# FlatSat_Final.net
KiCad netlist of a schematic drawn in EAGLE
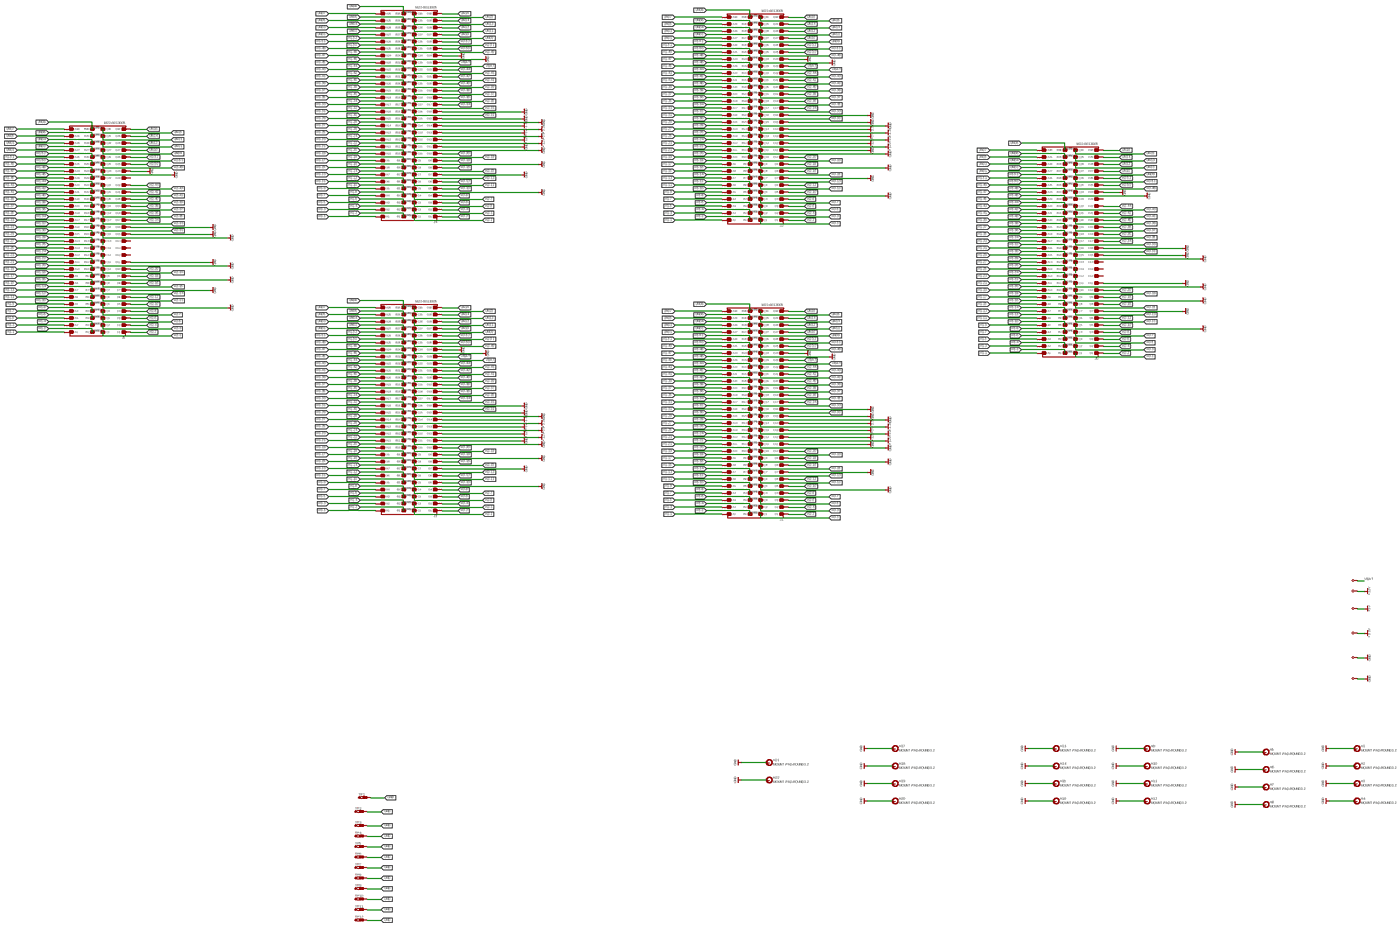
[diagram p0: schematic, sheet 1, overview]
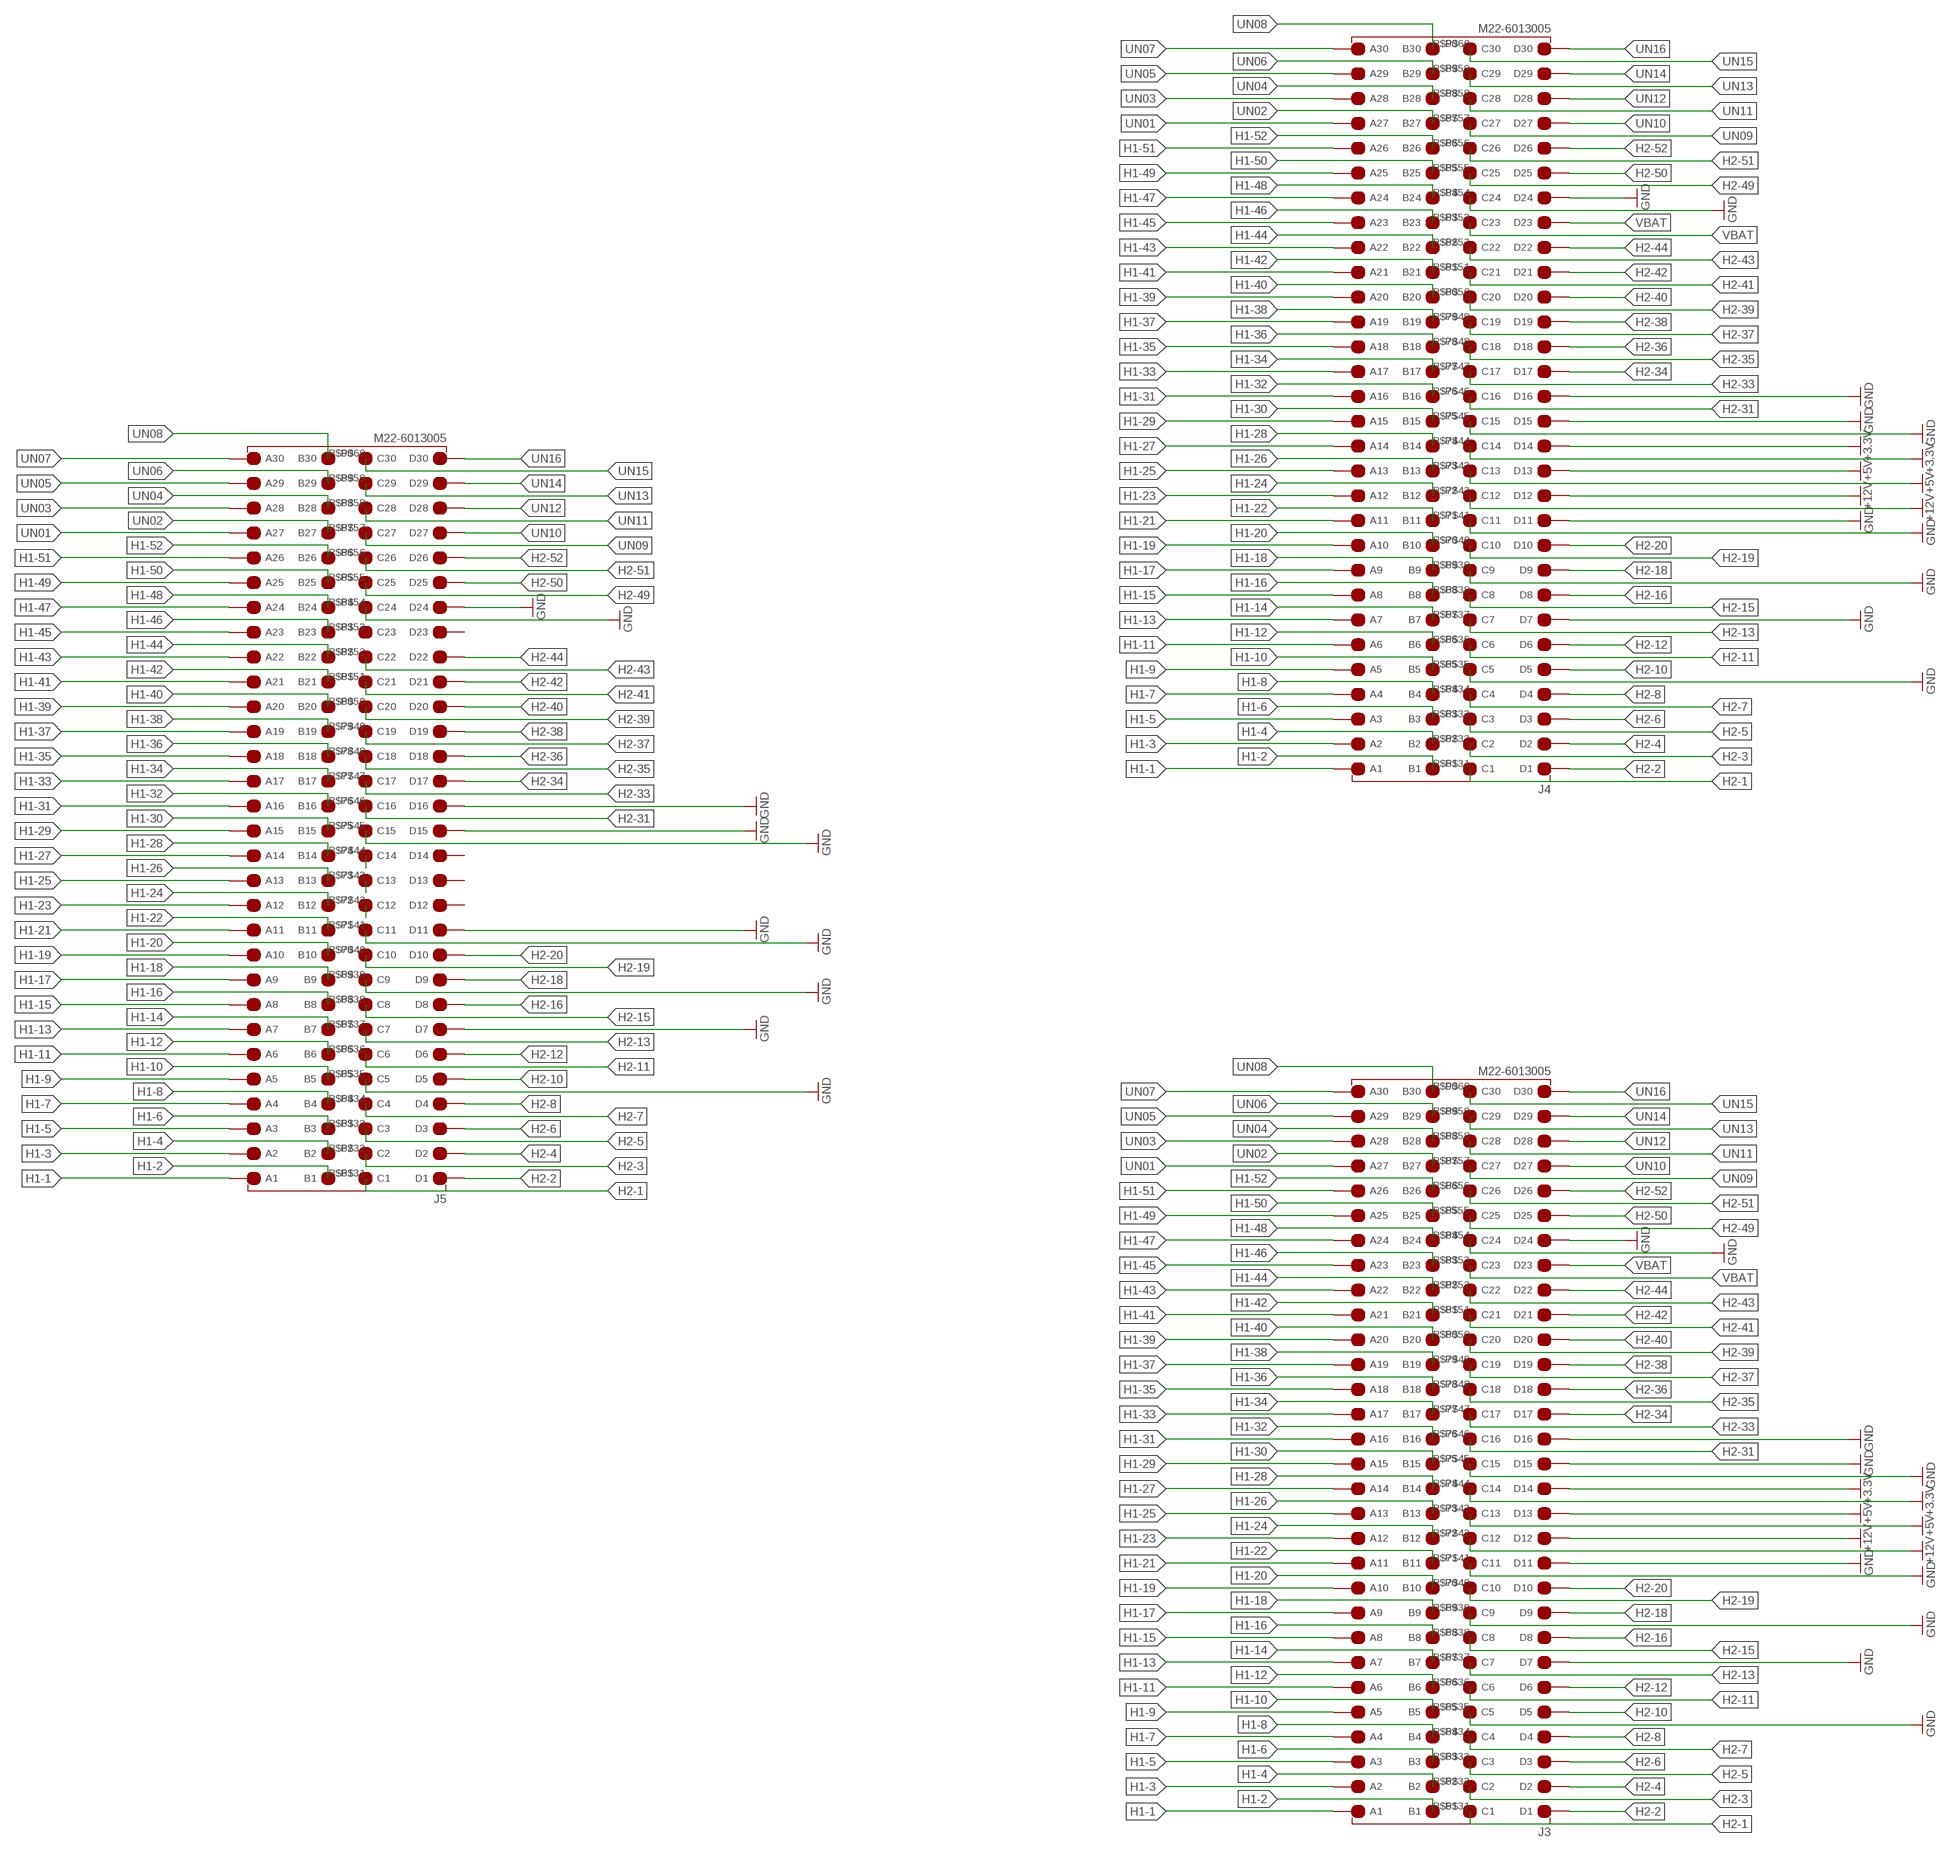
[diagram p1: schematic, sheet 1, part 1 of 5]
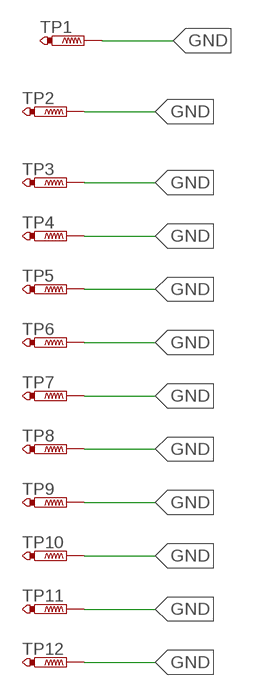
[diagram p2: schematic, sheet 1, part 2 of 5]
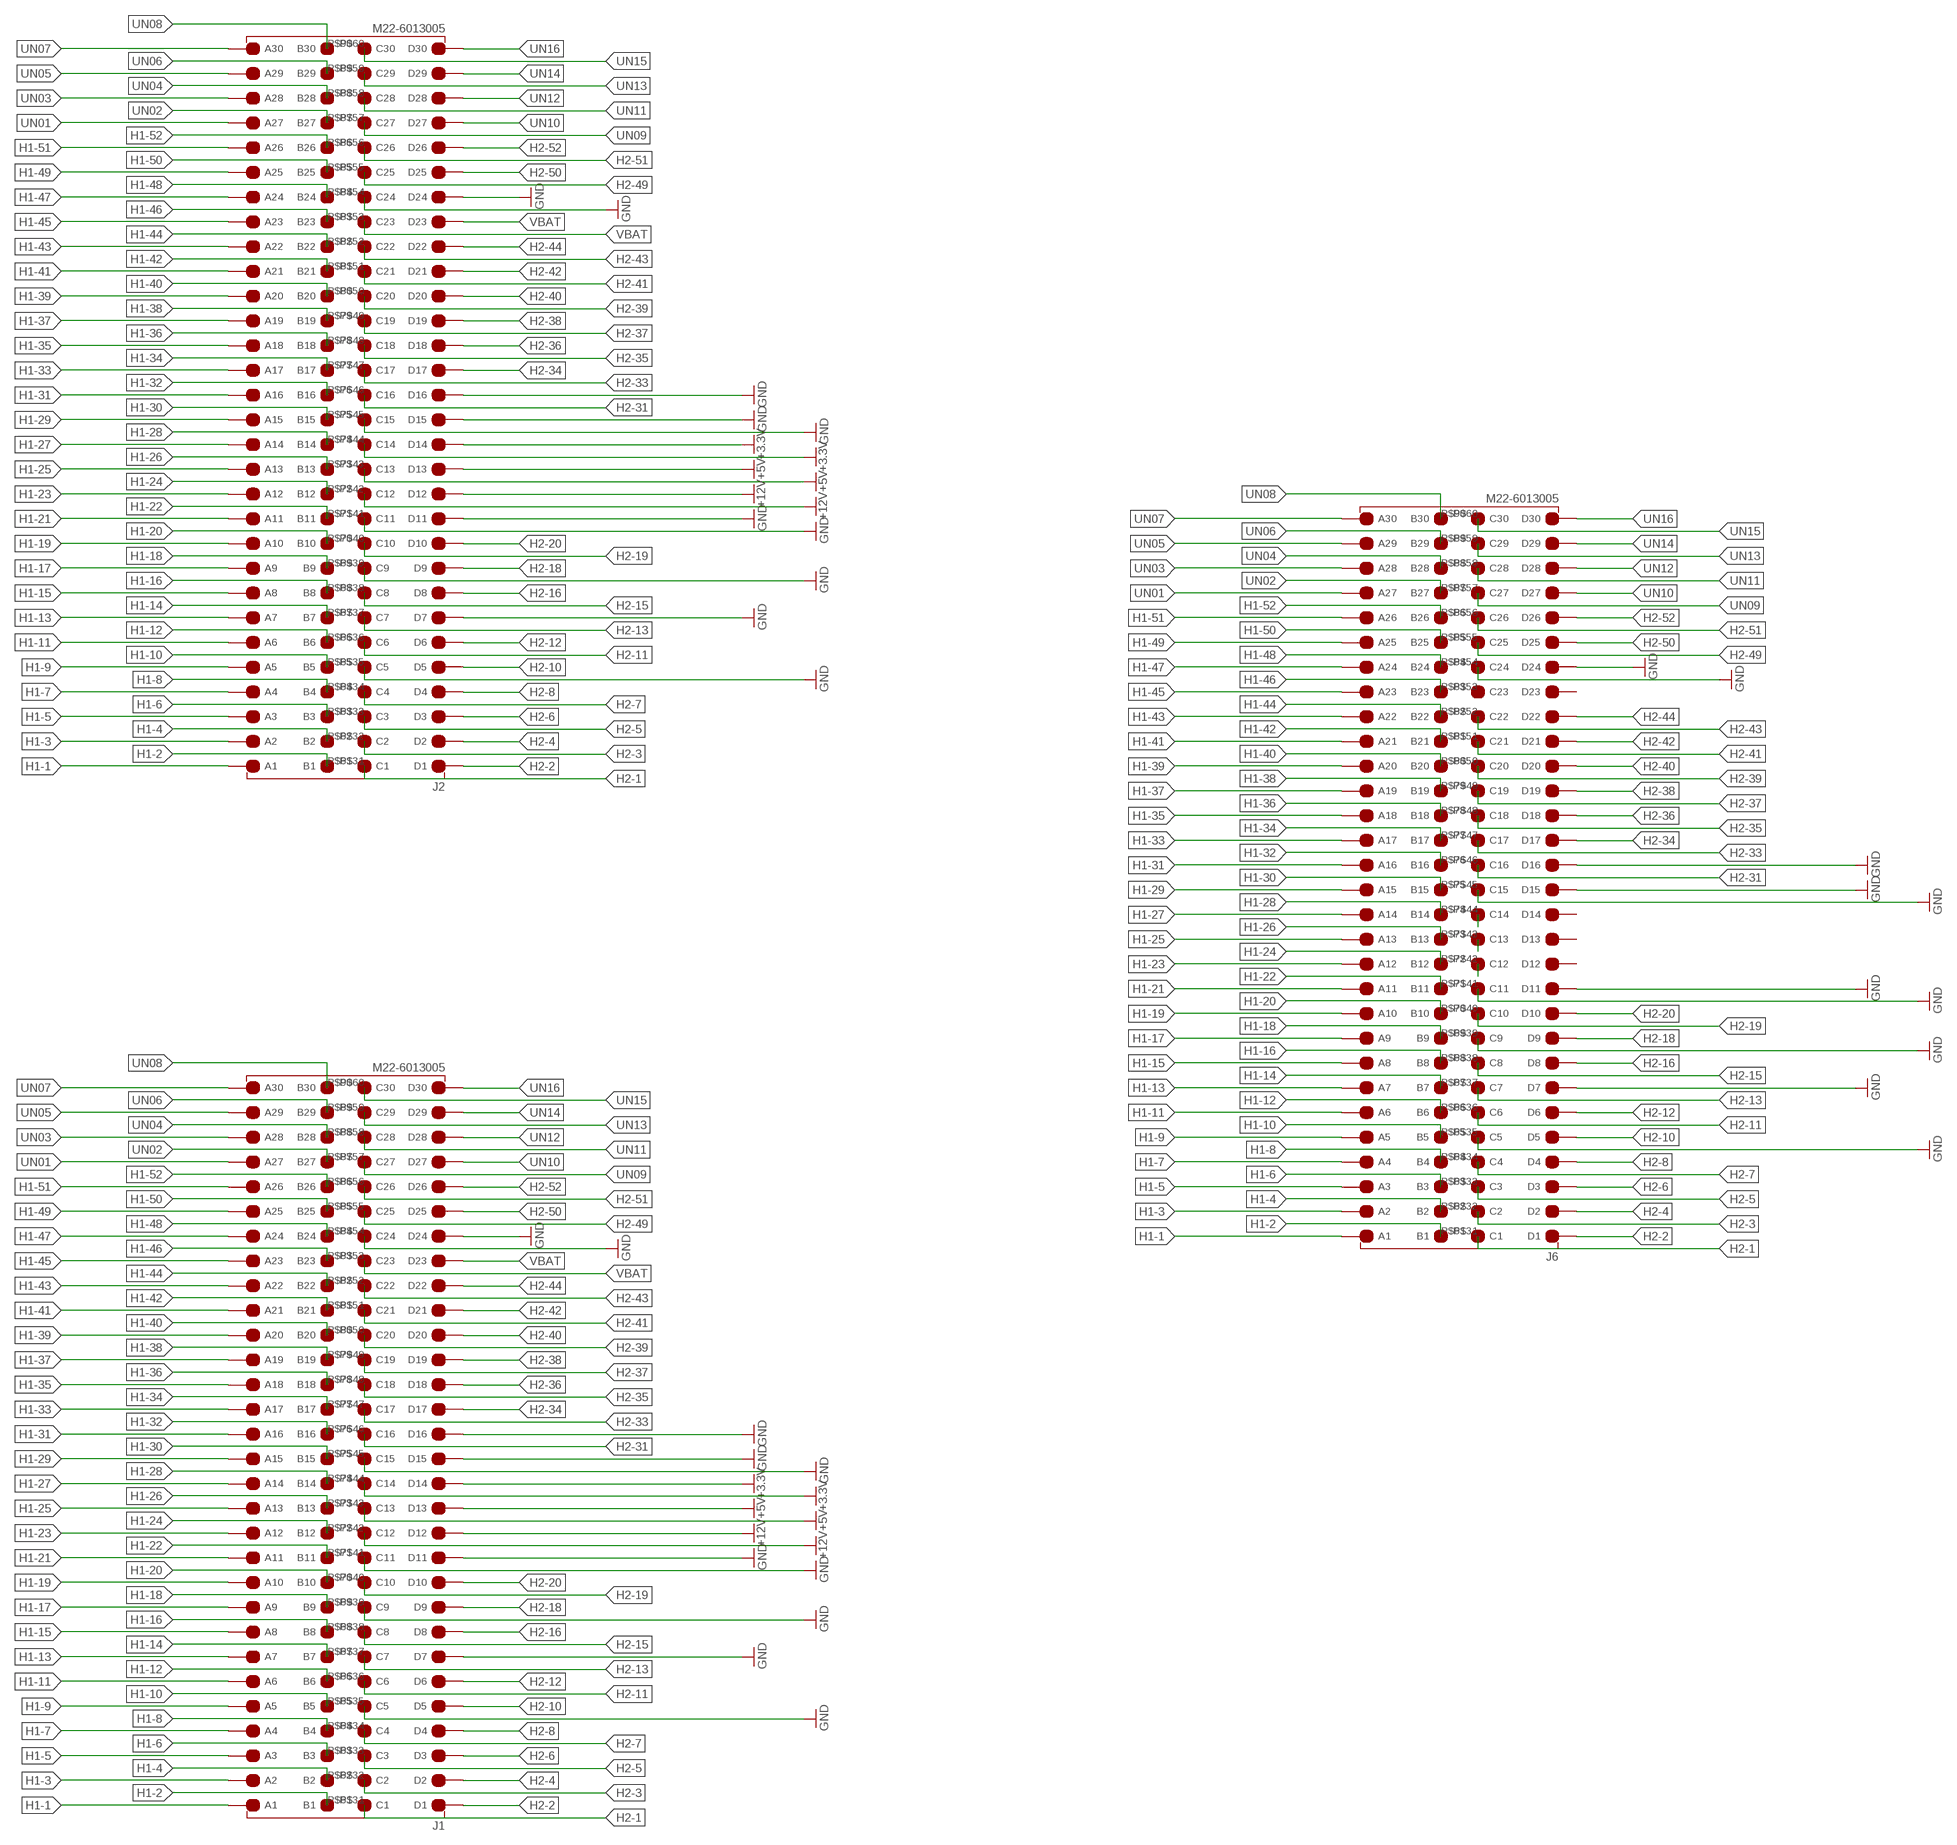
[diagram p3: schematic, sheet 1, part 3 of 5]
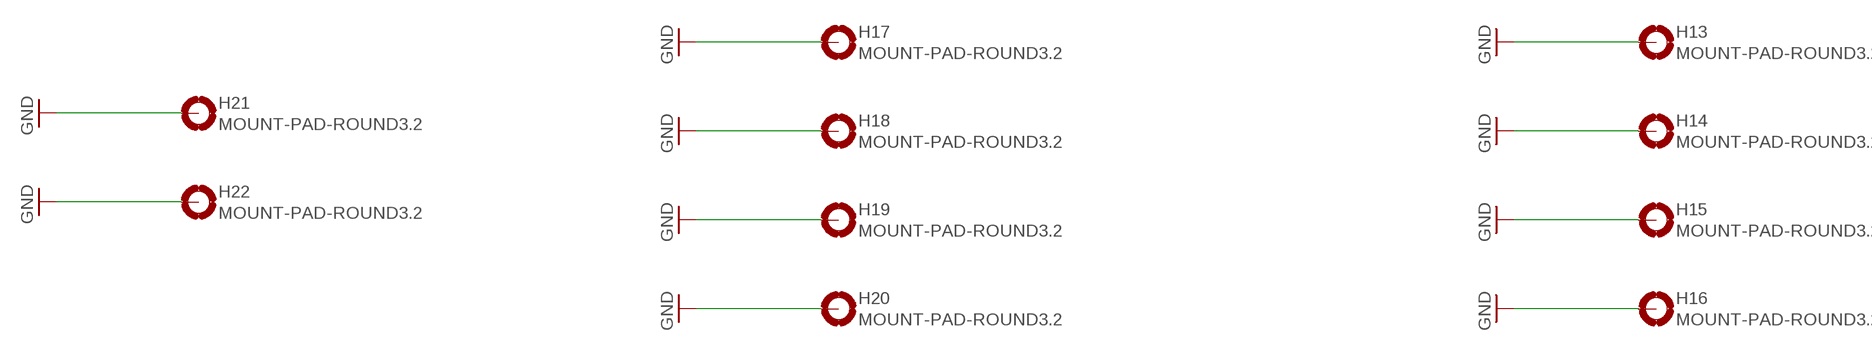
[diagram p4: schematic, sheet 1, part 4 of 5]
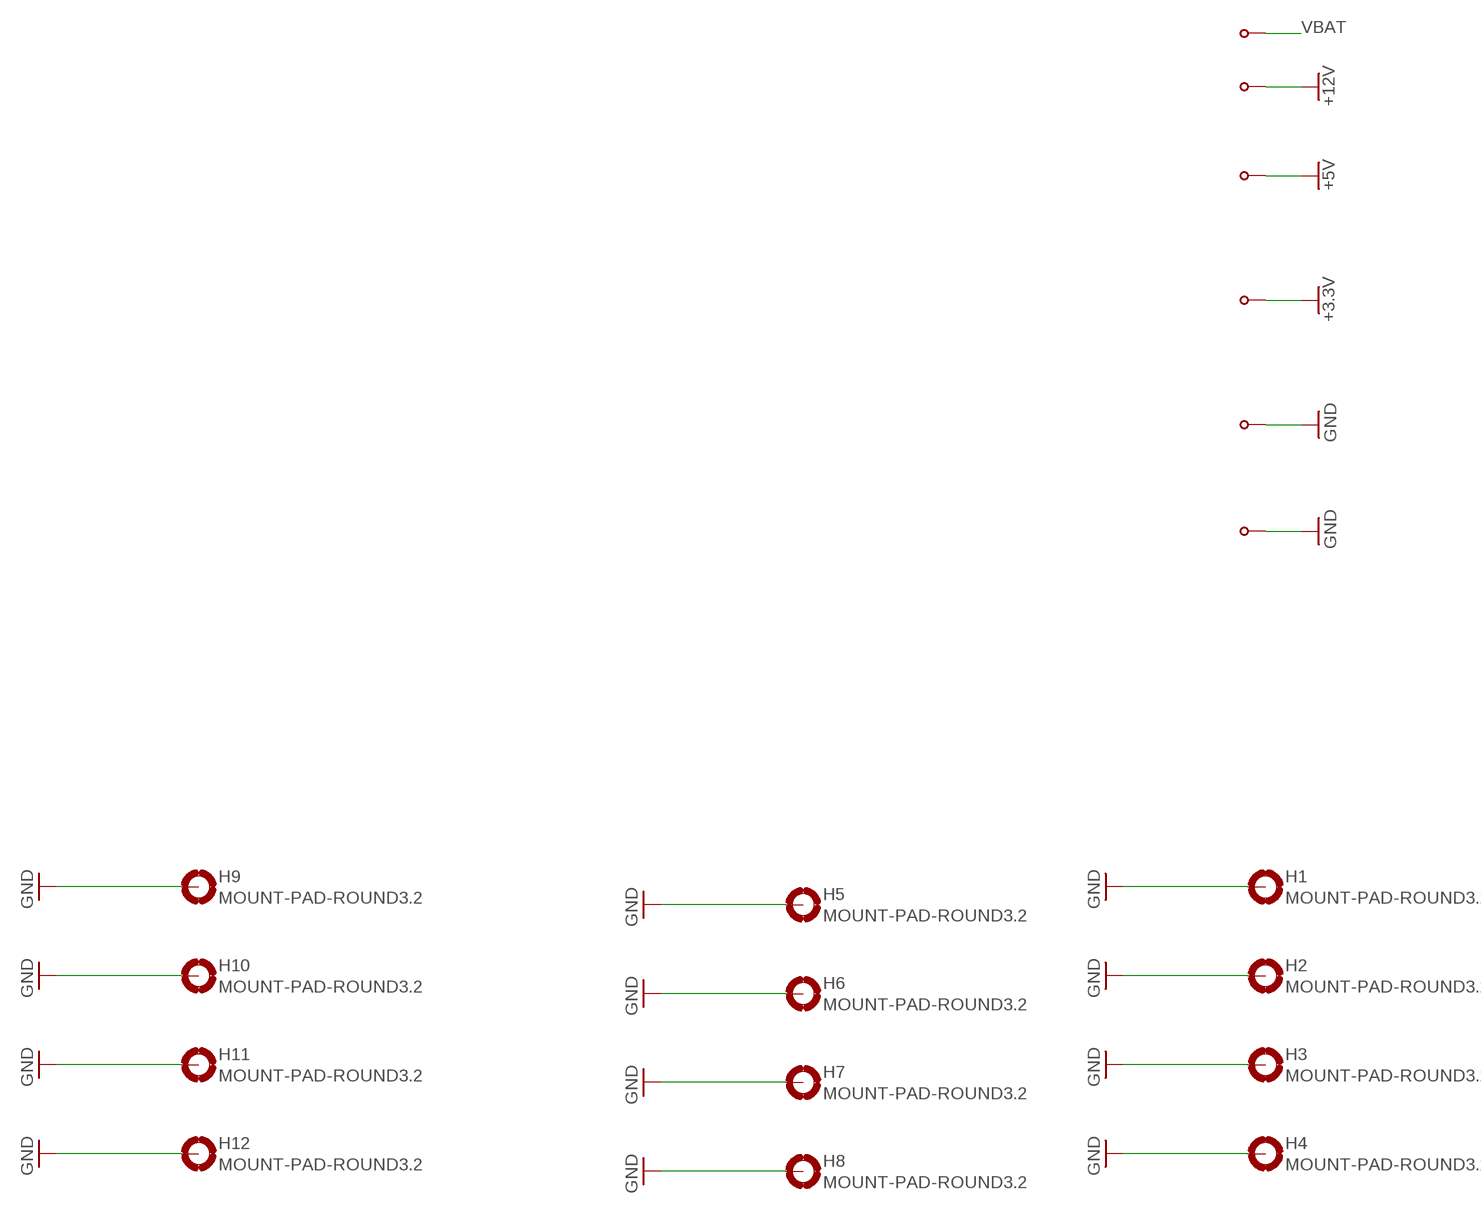
[diagram p5: schematic, sheet 1, part 5 of 5]

(export (version "E")
  (design (tool "Eeschema 10.0.6"))
  (components
    (comp (ref "H1")
      (value "MOUNT-PAD-ROUND3.2")
      (footprint "eagle-import:3,2-PAD")
      (libsource (lib "eagle-import") (part "MOUNT-PAD-ROUND3.2"))
    )
    (comp (ref "H2")
      (value "MOUNT-PAD-ROUND3.2")
      (footprint "eagle-import:3,2-PAD")
      (libsource (lib "eagle-import") (part "MOUNT-PAD-ROUND3.2"))
    )
    (comp (ref "H3")
      (value "MOUNT-PAD-ROUND3.2")
      (footprint "eagle-import:3,2-PAD")
      (libsource (lib "eagle-import") (part "MOUNT-PAD-ROUND3.2"))
    )
    (comp (ref "H4")
      (value "MOUNT-PAD-ROUND3.2")
      (footprint "eagle-import:3,2-PAD")
      (libsource (lib "eagle-import") (part "MOUNT-PAD-ROUND3.2"))
    )
    (comp (ref "H5")
      (value "MOUNT-PAD-ROUND3.2")
      (footprint "eagle-import:3,2-PAD")
      (libsource (lib "eagle-import") (part "MOUNT-PAD-ROUND3.2"))
    )
    (comp (ref "H6")
      (value "MOUNT-PAD-ROUND3.2")
      (footprint "eagle-import:3,2-PAD")
      (libsource (lib "eagle-import") (part "MOUNT-PAD-ROUND3.2"))
    )
    (comp (ref "H7")
      (value "MOUNT-PAD-ROUND3.2")
      (footprint "eagle-import:3,2-PAD")
      (libsource (lib "eagle-import") (part "MOUNT-PAD-ROUND3.2"))
    )
    (comp (ref "H8")
      (value "MOUNT-PAD-ROUND3.2")
      (footprint "eagle-import:3,2-PAD")
      (libsource (lib "eagle-import") (part "MOUNT-PAD-ROUND3.2"))
    )
    (comp (ref "H9")
      (value "MOUNT-PAD-ROUND3.2")
      (footprint "eagle-import:3,2-PAD")
      (libsource (lib "eagle-import") (part "MOUNT-PAD-ROUND3.2"))
    )
    (comp (ref "H10")
      (value "MOUNT-PAD-ROUND3.2")
      (footprint "eagle-import:3,2-PAD")
      (libsource (lib "eagle-import") (part "MOUNT-PAD-ROUND3.2"))
    )
    (comp (ref "H11")
      (value "MOUNT-PAD-ROUND3.2")
      (footprint "eagle-import:3,2-PAD")
      (libsource (lib "eagle-import") (part "MOUNT-PAD-ROUND3.2"))
    )
    (comp (ref "H12")
      (value "MOUNT-PAD-ROUND3.2")
      (footprint "eagle-import:3,2-PAD")
      (libsource (lib "eagle-import") (part "MOUNT-PAD-ROUND3.2"))
    )
    (comp (ref "H13")
      (value "MOUNT-PAD-ROUND3.2")
      (footprint "eagle-import:3,2-PAD")
      (libsource (lib "eagle-import") (part "MOUNT-PAD-ROUND3.2"))
    )
    (comp (ref "H14")
      (value "MOUNT-PAD-ROUND3.2")
      (footprint "eagle-import:3,2-PAD")
      (libsource (lib "eagle-import") (part "MOUNT-PAD-ROUND3.2"))
    )
    (comp (ref "H15")
      (value "MOUNT-PAD-ROUND3.2")
      (footprint "eagle-import:3,2-PAD")
      (libsource (lib "eagle-import") (part "MOUNT-PAD-ROUND3.2"))
    )
    (comp (ref "H16")
      (value "MOUNT-PAD-ROUND3.2")
      (footprint "eagle-import:3,2-PAD")
      (libsource (lib "eagle-import") (part "MOUNT-PAD-ROUND3.2"))
    )
    (comp (ref "H17")
      (value "MOUNT-PAD-ROUND3.2")
      (footprint "eagle-import:3,2-PAD")
      (libsource (lib "eagle-import") (part "MOUNT-PAD-ROUND3.2"))
    )
    (comp (ref "H18")
      (value "MOUNT-PAD-ROUND3.2")
      (footprint "eagle-import:3,2-PAD")
      (libsource (lib "eagle-import") (part "MOUNT-PAD-ROUND3.2"))
    )
    (comp (ref "H19")
      (value "MOUNT-PAD-ROUND3.2")
      (footprint "eagle-import:3,2-PAD")
      (libsource (lib "eagle-import") (part "MOUNT-PAD-ROUND3.2"))
    )
    (comp (ref "H20")
      (value "MOUNT-PAD-ROUND3.2")
      (footprint "eagle-import:3,2-PAD")
      (libsource (lib "eagle-import") (part "MOUNT-PAD-ROUND3.2"))
    )
    (comp (ref "H21")
      (value "MOUNT-PAD-ROUND3.2")
      (footprint "eagle-import:3,2-PAD")
      (libsource (lib "eagle-import") (part "MOUNT-PAD-ROUND3.2"))
    )
    (comp (ref "H22")
      (value "MOUNT-PAD-ROUND3.2")
      (footprint "eagle-import:3,2-PAD")
      (libsource (lib "eagle-import") (part "MOUNT-PAD-ROUND3.2"))
    )
    (comp (ref "J1")
      (value "M22-6013005")
      (footprint "eagle-import:RHDR120W55P200_4X30_6020X820X9")
      (libsource (lib "eagle-import") (part "M22-6013005"))
    )
    (comp (ref "J2")
      (value "M22-6013005")
      (footprint "eagle-import:RHDR120W55P200_4X30_6020X820X9")
      (libsource (lib "eagle-import") (part "M22-6013005"))
    )
    (comp (ref "J3")
      (value "M22-6013005")
      (footprint "eagle-import:RHDR120W55P200_4X30_6020X820X9")
      (libsource (lib "eagle-import") (part "M22-6013005"))
    )
    (comp (ref "J4")
      (value "M22-6013005")
      (footprint "eagle-import:RHDR120W55P200_4X30_6020X820X9")
      (libsource (lib "eagle-import") (part "M22-6013005"))
    )
    (comp (ref "J5")
      (value "M22-6013005")
      (footprint "eagle-import:RHDR120W55P200_4X30_6020X820X9")
      (libsource (lib "eagle-import") (part "M22-6013005"))
    )
    (comp (ref "J6")
      (value "M22-6013005")
      (footprint "eagle-import:RHDR120W55P200_4X30_6020X820X9")
      (libsource (lib "eagle-import") (part "M22-6013005"))
    )
    (comp (ref "TP1")
      (value "PTR1PAD1-13")
      (footprint "eagle-import:P1-13")
      (libsource (lib "eagle-import") (part "PTR1PAD1-13"))
    )
    (comp (ref "TP2")
      (value "PTR1PAD1-13")
      (footprint "eagle-import:P1-13")
      (libsource (lib "eagle-import") (part "PTR1PAD1-13"))
    )
    (comp (ref "TP3")
      (value "PTR1PAD1-13")
      (footprint "eagle-import:P1-13")
      (libsource (lib "eagle-import") (part "PTR1PAD1-13"))
    )
    (comp (ref "TP4")
      (value "PTR1PAD1-13")
      (footprint "eagle-import:P1-13")
      (libsource (lib "eagle-import") (part "PTR1PAD1-13"))
    )
    (comp (ref "TP5")
      (value "PTR1PAD1-13")
      (footprint "eagle-import:P1-13")
      (libsource (lib "eagle-import") (part "PTR1PAD1-13"))
    )
    (comp (ref "TP6")
      (value "PTR1PAD1-13")
      (footprint "eagle-import:P1-13")
      (libsource (lib "eagle-import") (part "PTR1PAD1-13"))
    )
    (comp (ref "TP7")
      (value "PTR1PAD1-13")
      (footprint "eagle-import:P1-13")
      (libsource (lib "eagle-import") (part "PTR1PAD1-13"))
    )
    (comp (ref "TP8")
      (value "PTR1PAD1-13")
      (footprint "eagle-import:P1-13")
      (libsource (lib "eagle-import") (part "PTR1PAD1-13"))
    )
    (comp (ref "TP9")
      (value "PTR1PAD1-13")
      (footprint "eagle-import:P1-13")
      (libsource (lib "eagle-import") (part "PTR1PAD1-13"))
    )
    (comp (ref "TP10")
      (value "PTR1PAD1-13")
      (footprint "eagle-import:P1-13")
      (libsource (lib "eagle-import") (part "PTR1PAD1-13"))
    )
    (comp (ref "TP11")
      (value "PTR1PAD1-13")
      (footprint "eagle-import:P1-13")
      (libsource (lib "eagle-import") (part "PTR1PAD1-13"))
    )
    (comp (ref "TP12")
      (value "PTR1PAD1-13")
      (footprint "eagle-import:P1-13")
      (libsource (lib "eagle-import") (part "PTR1PAD1-13"))
    )
    (comp (ref "U$1")
      (value "BANANA-JACK")
      (footprint "eagle-import:BANANA-PRINT")
      (libsource (lib "eagle-import") (part "BANANA-JACK"))
    )
    (comp (ref "U$2")
      (value "BANANA-JACK")
      (footprint "eagle-import:BANANA-PRINT")
      (libsource (lib "eagle-import") (part "BANANA-JACK"))
    )
    (comp (ref "U$3")
      (value "BANANA-JACK")
      (footprint "eagle-import:BANANA-PRINT")
      (libsource (lib "eagle-import") (part "BANANA-JACK"))
    )
    (comp (ref "U$4")
      (value "BANANA-JACK")
      (footprint "eagle-import:BANANA-PRINT")
      (libsource (lib "eagle-import") (part "BANANA-JACK"))
    )
    (comp (ref "U$5")
      (value "BANANA-JACK")
      (footprint "eagle-import:BANANA-PRINT")
      (libsource (lib "eagle-import") (part "BANANA-JACK"))
    )
    (comp (ref "U$6")
      (value "BANANA-JACK")
      (footprint "eagle-import:BANANA-PRINT")
      (libsource (lib "eagle-import") (part "BANANA-JACK"))
    )
  )
  (nets
    (net (code "1") (name "+3.3V") (class "Default")
      (node (ref "J1") (pin "P$14") (pinfunction "D14_P$14") (pintype "passive"))
      (node (ref "J1") (pin "P$44") (pinfunction "C14_P$44") (pintype "passive"))
      (node (ref "J2") (pin "P$14") (pinfunction "D14_P$14") (pintype "passive"))
      (node (ref "J2") (pin "P$44") (pinfunction "C14_P$44") (pintype "passive"))
      (node (ref "J3") (pin "P$14") (pinfunction "D14_P$14") (pintype "passive"))
      (node (ref "J3") (pin "P$44") (pinfunction "C14_P$44") (pintype "passive"))
      (node (ref "J4") (pin "P$14") (pinfunction "D14_P$14") (pintype "passive"))
      (node (ref "J4") (pin "P$44") (pinfunction "C14_P$44") (pintype "passive"))
      (node (ref "U$3") (pin "P$1") (pinfunction "PIN_P$1") (pintype "bidirectional"))
    )
    (net (code "2") (name "+5V") (class "Default")
      (node (ref "J1") (pin "P$13") (pinfunction "D13_P$13") (pintype "passive"))
      (node (ref "J1") (pin "P$43") (pinfunction "C13_P$43") (pintype "passive"))
      (node (ref "J2") (pin "P$13") (pinfunction "D13_P$13") (pintype "passive"))
      (node (ref "J2") (pin "P$43") (pinfunction "C13_P$43") (pintype "passive"))
      (node (ref "J3") (pin "P$13") (pinfunction "D13_P$13") (pintype "passive"))
      (node (ref "J3") (pin "P$43") (pinfunction "C13_P$43") (pintype "passive"))
      (node (ref "J4") (pin "P$13") (pinfunction "D13_P$13") (pintype "passive"))
      (node (ref "J4") (pin "P$43") (pinfunction "C13_P$43") (pintype "passive"))
      (node (ref "U$2") (pin "P$1") (pinfunction "PIN_P$1") (pintype "bidirectional"))
    )
    (net (code "3") (name "+12V") (class "Default")
      (node (ref "J1") (pin "P$12") (pinfunction "D12_P$12") (pintype "passive"))
      (node (ref "J1") (pin "P$42") (pinfunction "C12_P$42") (pintype "passive"))
      (node (ref "J2") (pin "P$12") (pinfunction "D12_P$12") (pintype "passive"))
      (node (ref "J2") (pin "P$42") (pinfunction "C12_P$42") (pintype "passive"))
      (node (ref "J3") (pin "P$12") (pinfunction "D12_P$12") (pintype "passive"))
      (node (ref "J3") (pin "P$42") (pinfunction "C12_P$42") (pintype "passive"))
      (node (ref "J4") (pin "P$12") (pinfunction "D12_P$12") (pintype "passive"))
      (node (ref "J4") (pin "P$42") (pinfunction "C12_P$42") (pintype "passive"))
      (node (ref "U$1") (pin "P$1") (pinfunction "PIN_P$1") (pintype "bidirectional"))
    )
    (net (code "4") (name "GND") (class "Default")
      (node (ref "J1") (pin "P$11") (pinfunction "D11_P$11") (pintype "passive"))
      (node (ref "J1") (pin "P$15") (pinfunction "D15_P$15") (pintype "passive"))
      (node (ref "J1") (pin "P$16") (pinfunction "D16_P$16") (pintype "passive"))
      (node (ref "J1") (pin "P$24") (pinfunction "D24_P$24") (pintype "passive"))
      (node (ref "J1") (pin "P$35") (pinfunction "C5_P$35") (pintype "passive"))
      (node (ref "J1") (pin "P$39") (pinfunction "C9_P$39") (pintype "passive"))
      (node (ref "J1") (pin "P$41") (pinfunction "C11_P$41") (pintype "passive"))
      (node (ref "J1") (pin "P$45") (pinfunction "C15_P$45") (pintype "passive"))
      (node (ref "J1") (pin "P$54") (pinfunction "C24_P$54") (pintype "passive"))
      (node (ref "J1") (pin "P$7") (pinfunction "D7_P$7") (pintype "passive"))
      (node (ref "J2") (pin "P$11") (pinfunction "D11_P$11") (pintype "passive"))
      (node (ref "J2") (pin "P$15") (pinfunction "D15_P$15") (pintype "passive"))
      (node (ref "J2") (pin "P$16") (pinfunction "D16_P$16") (pintype "passive"))
      (node (ref "J2") (pin "P$24") (pinfunction "D24_P$24") (pintype "passive"))
      (node (ref "J2") (pin "P$35") (pinfunction "C5_P$35") (pintype "passive"))
      (node (ref "J2") (pin "P$39") (pinfunction "C9_P$39") (pintype "passive"))
      (node (ref "J2") (pin "P$41") (pinfunction "C11_P$41") (pintype "passive"))
      (node (ref "J2") (pin "P$45") (pinfunction "C15_P$45") (pintype "passive"))
      (node (ref "J2") (pin "P$54") (pinfunction "C24_P$54") (pintype "passive"))
      (node (ref "J2") (pin "P$7") (pinfunction "D7_P$7") (pintype "passive"))
      (node (ref "J3") (pin "P$11") (pinfunction "D11_P$11") (pintype "passive"))
      (node (ref "J3") (pin "P$15") (pinfunction "D15_P$15") (pintype "passive"))
      (node (ref "J3") (pin "P$16") (pinfunction "D16_P$16") (pintype "passive"))
      (node (ref "J3") (pin "P$24") (pinfunction "D24_P$24") (pintype "passive"))
      (node (ref "J3") (pin "P$35") (pinfunction "C5_P$35") (pintype "passive"))
      (node (ref "J3") (pin "P$39") (pinfunction "C9_P$39") (pintype "passive"))
      (node (ref "J3") (pin "P$41") (pinfunction "C11_P$41") (pintype "passive"))
      (node (ref "J3") (pin "P$45") (pinfunction "C15_P$45") (pintype "passive"))
      (node (ref "J3") (pin "P$54") (pinfunction "C24_P$54") (pintype "passive"))
      (node (ref "J3") (pin "P$7") (pinfunction "D7_P$7") (pintype "passive"))
      (node (ref "J4") (pin "P$11") (pinfunction "D11_P$11") (pintype "passive"))
      (node (ref "J4") (pin "P$15") (pinfunction "D15_P$15") (pintype "passive"))
      (node (ref "J4") (pin "P$16") (pinfunction "D16_P$16") (pintype "passive"))
      (node (ref "J4") (pin "P$24") (pinfunction "D24_P$24") (pintype "passive"))
      (node (ref "J4") (pin "P$35") (pinfunction "C5_P$35") (pintype "passive"))
      (node (ref "J4") (pin "P$39") (pinfunction "C9_P$39") (pintype "passive"))
      (node (ref "J4") (pin "P$41") (pinfunction "C11_P$41") (pintype "passive"))
      (node (ref "J4") (pin "P$45") (pinfunction "C15_P$45") (pintype "passive"))
      (node (ref "J4") (pin "P$54") (pinfunction "C24_P$54") (pintype "passive"))
      (node (ref "J4") (pin "P$7") (pinfunction "D7_P$7") (pintype "passive"))
      (node (ref "J5") (pin "P$11") (pinfunction "D11_P$11") (pintype "passive"))
      (node (ref "J5") (pin "P$15") (pinfunction "D15_P$15") (pintype "passive"))
      (node (ref "J5") (pin "P$16") (pinfunction "D16_P$16") (pintype "passive"))
      (node (ref "J5") (pin "P$24") (pinfunction "D24_P$24") (pintype "passive"))
      (node (ref "J5") (pin "P$35") (pinfunction "C5_P$35") (pintype "passive"))
      (node (ref "J5") (pin "P$39") (pinfunction "C9_P$39") (pintype "passive"))
      (node (ref "J5") (pin "P$41") (pinfunction "C11_P$41") (pintype "passive"))
      (node (ref "J5") (pin "P$45") (pinfunction "C15_P$45") (pintype "passive"))
      (node (ref "J5") (pin "P$54") (pinfunction "C24_P$54") (pintype "passive"))
      (node (ref "J5") (pin "P$7") (pinfunction "D7_P$7") (pintype "passive"))
      (node (ref "J6") (pin "P$11") (pinfunction "D11_P$11") (pintype "passive"))
      (node (ref "J6") (pin "P$15") (pinfunction "D15_P$15") (pintype "passive"))
      (node (ref "J6") (pin "P$16") (pinfunction "D16_P$16") (pintype "passive"))
      (node (ref "J6") (pin "P$24") (pinfunction "D24_P$24") (pintype "passive"))
      (node (ref "J6") (pin "P$35") (pinfunction "C5_P$35") (pintype "passive"))
      (node (ref "J6") (pin "P$39") (pinfunction "C9_P$39") (pintype "passive"))
      (node (ref "J6") (pin "P$41") (pinfunction "C11_P$41") (pintype "passive"))
      (node (ref "J6") (pin "P$45") (pinfunction "C15_P$45") (pintype "passive"))
      (node (ref "J6") (pin "P$54") (pinfunction "C24_P$54") (pintype "passive"))
      (node (ref "J6") (pin "P$7") (pinfunction "D7_P$7") (pintype "passive"))
      (node (ref "TP1") (pin "TP") (pinfunction "TP_TP") (pintype "input"))
      (node (ref "TP10") (pin "TP") (pinfunction "TP_TP") (pintype "input"))
      (node (ref "TP11") (pin "TP") (pinfunction "TP_TP") (pintype "input"))
      (node (ref "TP12") (pin "TP") (pinfunction "TP_TP") (pintype "input"))
      (node (ref "TP2") (pin "TP") (pinfunction "TP_TP") (pintype "input"))
      (node (ref "TP3") (pin "TP") (pinfunction "TP_TP") (pintype "input"))
      (node (ref "TP4") (pin "TP") (pinfunction "TP_TP") (pintype "input"))
      (node (ref "TP5") (pin "TP") (pinfunction "TP_TP") (pintype "input"))
      (node (ref "TP6") (pin "TP") (pinfunction "TP_TP") (pintype "input"))
      (node (ref "TP7") (pin "TP") (pinfunction "TP_TP") (pintype "input"))
      (node (ref "TP8") (pin "TP") (pinfunction "TP_TP") (pintype "input"))
      (node (ref "TP9") (pin "TP") (pinfunction "TP_TP") (pintype "input"))
      (node (ref "U$4") (pin "P$1") (pinfunction "PIN_P$1") (pintype "bidirectional"))
      (node (ref "U$5") (pin "P$1") (pinfunction "PIN_P$1") (pintype "bidirectional"))
    )
    (net (code "5") (name "H1-1") (class "Default")
      (node (ref "J1") (pin "P$91") (pinfunction "A1_P$91") (pintype "passive"))
      (node (ref "J2") (pin "P$91") (pinfunction "A1_P$91") (pintype "passive"))
      (node (ref "J3") (pin "P$91") (pinfunction "A1_P$91") (pintype "passive"))
      (node (ref "J4") (pin "P$91") (pinfunction "A1_P$91") (pintype "passive"))
      (node (ref "J5") (pin "P$91") (pinfunction "A1_P$91") (pintype "passive"))
      (node (ref "J6") (pin "P$91") (pinfunction "A1_P$91") (pintype "passive"))
    )
    (net (code "6") (name "H1-2") (class "Default")
      (node (ref "J1") (pin "P$61") (pinfunction "B1_P$61") (pintype "passive"))
      (node (ref "J2") (pin "P$61") (pinfunction "B1_P$61") (pintype "passive"))
      (node (ref "J3") (pin "P$61") (pinfunction "B1_P$61") (pintype "passive"))
      (node (ref "J4") (pin "P$61") (pinfunction "B1_P$61") (pintype "passive"))
      (node (ref "J5") (pin "P$61") (pinfunction "B1_P$61") (pintype "passive"))
      (node (ref "J6") (pin "P$61") (pinfunction "B1_P$61") (pintype "passive"))
    )
    (net (code "7") (name "H1-3") (class "Default")
      (node (ref "J1") (pin "P$92") (pinfunction "A2_P$92") (pintype "passive"))
      (node (ref "J2") (pin "P$92") (pinfunction "A2_P$92") (pintype "passive"))
      (node (ref "J3") (pin "P$92") (pinfunction "A2_P$92") (pintype "passive"))
      (node (ref "J4") (pin "P$92") (pinfunction "A2_P$92") (pintype "passive"))
      (node (ref "J5") (pin "P$92") (pinfunction "A2_P$92") (pintype "passive"))
      (node (ref "J6") (pin "P$92") (pinfunction "A2_P$92") (pintype "passive"))
    )
    (net (code "8") (name "H1-4") (class "Default")
      (node (ref "J1") (pin "P$62") (pinfunction "B2_P$62") (pintype "passive"))
      (node (ref "J2") (pin "P$62") (pinfunction "B2_P$62") (pintype "passive"))
      (node (ref "J3") (pin "P$62") (pinfunction "B2_P$62") (pintype "passive"))
      (node (ref "J4") (pin "P$62") (pinfunction "B2_P$62") (pintype "passive"))
      (node (ref "J5") (pin "P$62") (pinfunction "B2_P$62") (pintype "passive"))
      (node (ref "J6") (pin "P$62") (pinfunction "B2_P$62") (pintype "passive"))
    )
    (net (code "9") (name "H1-5") (class "Default")
      (node (ref "J1") (pin "P$93") (pinfunction "A3_P$93") (pintype "passive"))
      (node (ref "J2") (pin "P$93") (pinfunction "A3_P$93") (pintype "passive"))
      (node (ref "J3") (pin "P$93") (pinfunction "A3_P$93") (pintype "passive"))
      (node (ref "J4") (pin "P$93") (pinfunction "A3_P$93") (pintype "passive"))
      (node (ref "J5") (pin "P$93") (pinfunction "A3_P$93") (pintype "passive"))
      (node (ref "J6") (pin "P$93") (pinfunction "A3_P$93") (pintype "passive"))
    )
    (net (code "10") (name "H1-6") (class "Default")
      (node (ref "J1") (pin "P$63") (pinfunction "B3_P$63") (pintype "passive"))
      (node (ref "J2") (pin "P$63") (pinfunction "B3_P$63") (pintype "passive"))
      (node (ref "J3") (pin "P$63") (pinfunction "B3_P$63") (pintype "passive"))
      (node (ref "J4") (pin "P$63") (pinfunction "B3_P$63") (pintype "passive"))
      (node (ref "J5") (pin "P$63") (pinfunction "B3_P$63") (pintype "passive"))
      (node (ref "J6") (pin "P$63") (pinfunction "B3_P$63") (pintype "passive"))
    )
    (net (code "11") (name "H1-7") (class "Default")
      (node (ref "J1") (pin "P$94") (pinfunction "A4_P$94") (pintype "passive"))
      (node (ref "J2") (pin "P$94") (pinfunction "A4_P$94") (pintype "passive"))
      (node (ref "J3") (pin "P$94") (pinfunction "A4_P$94") (pintype "passive"))
      (node (ref "J4") (pin "P$94") (pinfunction "A4_P$94") (pintype "passive"))
      (node (ref "J5") (pin "P$94") (pinfunction "A4_P$94") (pintype "passive"))
      (node (ref "J6") (pin "P$94") (pinfunction "A4_P$94") (pintype "passive"))
    )
    (net (code "12") (name "H1-8") (class "Default")
      (node (ref "J1") (pin "P$64") (pinfunction "B4_P$64") (pintype "passive"))
      (node (ref "J2") (pin "P$64") (pinfunction "B4_P$64") (pintype "passive"))
      (node (ref "J3") (pin "P$64") (pinfunction "B4_P$64") (pintype "passive"))
      (node (ref "J4") (pin "P$64") (pinfunction "B4_P$64") (pintype "passive"))
      (node (ref "J5") (pin "P$64") (pinfunction "B4_P$64") (pintype "passive"))
      (node (ref "J6") (pin "P$64") (pinfunction "B4_P$64") (pintype "passive"))
    )
    (net (code "13") (name "H1-9") (class "Default")
      (node (ref "J1") (pin "P$95") (pinfunction "A5_P$95") (pintype "passive"))
      (node (ref "J2") (pin "P$95") (pinfunction "A5_P$95") (pintype "passive"))
      (node (ref "J3") (pin "P$95") (pinfunction "A5_P$95") (pintype "passive"))
      (node (ref "J4") (pin "P$95") (pinfunction "A5_P$95") (pintype "passive"))
      (node (ref "J5") (pin "P$95") (pinfunction "A5_P$95") (pintype "passive"))
      (node (ref "J6") (pin "P$95") (pinfunction "A5_P$95") (pintype "passive"))
    )
    (net (code "14") (name "H1-10") (class "Default")
      (node (ref "J1") (pin "P$65") (pinfunction "B5_P$65") (pintype "passive"))
      (node (ref "J2") (pin "P$65") (pinfunction "B5_P$65") (pintype "passive"))
      (node (ref "J3") (pin "P$65") (pinfunction "B5_P$65") (pintype "passive"))
      (node (ref "J4") (pin "P$65") (pinfunction "B5_P$65") (pintype "passive"))
      (node (ref "J5") (pin "P$65") (pinfunction "B5_P$65") (pintype "passive"))
      (node (ref "J6") (pin "P$65") (pinfunction "B5_P$65") (pintype "passive"))
    )
    (net (code "15") (name "H1-11") (class "Default")
      (node (ref "J1") (pin "P$96") (pinfunction "A6_P$96") (pintype "passive"))
      (node (ref "J2") (pin "P$96") (pinfunction "A6_P$96") (pintype "passive"))
      (node (ref "J3") (pin "P$96") (pinfunction "A6_P$96") (pintype "passive"))
      (node (ref "J4") (pin "P$96") (pinfunction "A6_P$96") (pintype "passive"))
      (node (ref "J5") (pin "P$96") (pinfunction "A6_P$96") (pintype "passive"))
      (node (ref "J6") (pin "P$96") (pinfunction "A6_P$96") (pintype "passive"))
    )
    (net (code "16") (name "H1-12") (class "Default")
      (node (ref "J1") (pin "P$66") (pinfunction "B6_P$66") (pintype "passive"))
      (node (ref "J2") (pin "P$66") (pinfunction "B6_P$66") (pintype "passive"))
      (node (ref "J3") (pin "P$66") (pinfunction "B6_P$66") (pintype "passive"))
      (node (ref "J4") (pin "P$66") (pinfunction "B6_P$66") (pintype "passive"))
      (node (ref "J5") (pin "P$66") (pinfunction "B6_P$66") (pintype "passive"))
      (node (ref "J6") (pin "P$66") (pinfunction "B6_P$66") (pintype "passive"))
    )
    (net (code "17") (name "H1-13") (class "Default")
      (node (ref "J1") (pin "P$97") (pinfunction "A7_P$97") (pintype "passive"))
      (node (ref "J2") (pin "P$97") (pinfunction "A7_P$97") (pintype "passive"))
      (node (ref "J3") (pin "P$97") (pinfunction "A7_P$97") (pintype "passive"))
      (node (ref "J4") (pin "P$97") (pinfunction "A7_P$97") (pintype "passive"))
      (node (ref "J5") (pin "P$97") (pinfunction "A7_P$97") (pintype "passive"))
      (node (ref "J6") (pin "P$97") (pinfunction "A7_P$97") (pintype "passive"))
    )
    (net (code "18") (name "H1-14") (class "Default")
      (node (ref "J1") (pin "P$67") (pinfunction "B7_P$67") (pintype "passive"))
      (node (ref "J2") (pin "P$67") (pinfunction "B7_P$67") (pintype "passive"))
      (node (ref "J3") (pin "P$67") (pinfunction "B7_P$67") (pintype "passive"))
      (node (ref "J4") (pin "P$67") (pinfunction "B7_P$67") (pintype "passive"))
      (node (ref "J5") (pin "P$67") (pinfunction "B7_P$67") (pintype "passive"))
      (node (ref "J6") (pin "P$67") (pinfunction "B7_P$67") (pintype "passive"))
    )
    (net (code "19") (name "H1-15") (class "Default")
      (node (ref "J1") (pin "P$98") (pinfunction "A8_P$98") (pintype "passive"))
      (node (ref "J2") (pin "P$98") (pinfunction "A8_P$98") (pintype "passive"))
      (node (ref "J3") (pin "P$98") (pinfunction "A8_P$98") (pintype "passive"))
      (node (ref "J4") (pin "P$98") (pinfunction "A8_P$98") (pintype "passive"))
      (node (ref "J5") (pin "P$98") (pinfunction "A8_P$98") (pintype "passive"))
      (node (ref "J6") (pin "P$98") (pinfunction "A8_P$98") (pintype "passive"))
    )
    (net (code "20") (name "H1-16") (class "Default")
      (node (ref "J1") (pin "P$68") (pinfunction "B8_P$68") (pintype "passive"))
      (node (ref "J2") (pin "P$68") (pinfunction "B8_P$68") (pintype "passive"))
      (node (ref "J3") (pin "P$68") (pinfunction "B8_P$68") (pintype "passive"))
      (node (ref "J4") (pin "P$68") (pinfunction "B8_P$68") (pintype "passive"))
      (node (ref "J5") (pin "P$68") (pinfunction "B8_P$68") (pintype "passive"))
      (node (ref "J6") (pin "P$68") (pinfunction "B8_P$68") (pintype "passive"))
    )
    (net (code "21") (name "H1-17") (class "Default")
      (node (ref "J1") (pin "P$99") (pinfunction "A9_P$99") (pintype "passive"))
      (node (ref "J2") (pin "P$99") (pinfunction "A9_P$99") (pintype "passive"))
      (node (ref "J3") (pin "P$99") (pinfunction "A9_P$99") (pintype "passive"))
      (node (ref "J4") (pin "P$99") (pinfunction "A9_P$99") (pintype "passive"))
      (node (ref "J5") (pin "P$99") (pinfunction "A9_P$99") (pintype "passive"))
      (node (ref "J6") (pin "P$99") (pinfunction "A9_P$99") (pintype "passive"))
    )
    (net (code "22") (name "H1-18") (class "Default")
      (node (ref "J1") (pin "P$69") (pinfunction "B9_P$69") (pintype "passive"))
      (node (ref "J2") (pin "P$69") (pinfunction "B9_P$69") (pintype "passive"))
      (node (ref "J3") (pin "P$69") (pinfunction "B9_P$69") (pintype "passive"))
      (node (ref "J4") (pin "P$69") (pinfunction "B9_P$69") (pintype "passive"))
      (node (ref "J5") (pin "P$69") (pinfunction "B9_P$69") (pintype "passive"))
      (node (ref "J6") (pin "P$69") (pinfunction "B9_P$69") (pintype "passive"))
    )
    (net (code "23") (name "H1-19") (class "Default")
      (node (ref "J1") (pin "P$100") (pinfunction "A10_P$100") (pintype "passive"))
      (node (ref "J2") (pin "P$100") (pinfunction "A10_P$100") (pintype "passive"))
      (node (ref "J3") (pin "P$100") (pinfunction "A10_P$100") (pintype "passive"))
      (node (ref "J4") (pin "P$100") (pinfunction "A10_P$100") (pintype "passive"))
      (node (ref "J5") (pin "P$100") (pinfunction "A10_P$100") (pintype "passive"))
      (node (ref "J6") (pin "P$100") (pinfunction "A10_P$100") (pintype "passive"))
    )
    (net (code "24") (name "H1-20") (class "Default")
      (node (ref "J1") (pin "P$70") (pinfunction "B10_P$70") (pintype "passive"))
      (node (ref "J2") (pin "P$70") (pinfunction "B10_P$70") (pintype "passive"))
      (node (ref "J3") (pin "P$70") (pinfunction "B10_P$70") (pintype "passive"))
      (node (ref "J4") (pin "P$70") (pinfunction "B10_P$70") (pintype "passive"))
      (node (ref "J5") (pin "P$70") (pinfunction "B10_P$70") (pintype "passive"))
      (node (ref "J6") (pin "P$70") (pinfunction "B10_P$70") (pintype "passive"))
    )
    (net (code "25") (name "H1-21") (class "Default")
      (node (ref "J1") (pin "P$101") (pinfunction "A11_P$101") (pintype "passive"))
      (node (ref "J2") (pin "P$101") (pinfunction "A11_P$101") (pintype "passive"))
      (node (ref "J3") (pin "P$101") (pinfunction "A11_P$101") (pintype "passive"))
      (node (ref "J4") (pin "P$101") (pinfunction "A11_P$101") (pintype "passive"))
      (node (ref "J5") (pin "P$101") (pinfunction "A11_P$101") (pintype "passive"))
      (node (ref "J6") (pin "P$101") (pinfunction "A11_P$101") (pintype "passive"))
    )
    (net (code "26") (name "H1-22") (class "Default")
      (node (ref "J1") (pin "P$71") (pinfunction "B11_P$71") (pintype "passive"))
      (node (ref "J2") (pin "P$71") (pinfunction "B11_P$71") (pintype "passive"))
      (node (ref "J3") (pin "P$71") (pinfunction "B11_P$71") (pintype "passive"))
      (node (ref "J4") (pin "P$71") (pinfunction "B11_P$71") (pintype "passive"))
      (node (ref "J5") (pin "P$71") (pinfunction "B11_P$71") (pintype "passive"))
      (node (ref "J6") (pin "P$71") (pinfunction "B11_P$71") (pintype "passive"))
    )
    (net (code "27") (name "H1-23") (class "Default")
      (node (ref "J1") (pin "P$102") (pinfunction "A12_P$102") (pintype "passive"))
      (node (ref "J2") (pin "P$102") (pinfunction "A12_P$102") (pintype "passive"))
      (node (ref "J3") (pin "P$102") (pinfunction "A12_P$102") (pintype "passive"))
      (node (ref "J4") (pin "P$102") (pinfunction "A12_P$102") (pintype "passive"))
      (node (ref "J5") (pin "P$102") (pinfunction "A12_P$102") (pintype "passive"))
      (node (ref "J6") (pin "P$102") (pinfunction "A12_P$102") (pintype "passive"))
    )
    (net (code "28") (name "H1-24") (class "Default")
      (node (ref "J1") (pin "P$72") (pinfunction "B12_P$72") (pintype "passive"))
      (node (ref "J2") (pin "P$72") (pinfunction "B12_P$72") (pintype "passive"))
      (node (ref "J3") (pin "P$72") (pinfunction "B12_P$72") (pintype "passive"))
      (node (ref "J4") (pin "P$72") (pinfunction "B12_P$72") (pintype "passive"))
      (node (ref "J5") (pin "P$72") (pinfunction "B12_P$72") (pintype "passive"))
      (node (ref "J6") (pin "P$72") (pinfunction "B12_P$72") (pintype "passive"))
    )
    (net (code "29") (name "H1-25") (class "Default")
      (node (ref "J1") (pin "P$103") (pinfunction "A13_P$103") (pintype "passive"))
      (node (ref "J2") (pin "P$103") (pinfunction "A13_P$103") (pintype "passive"))
      (node (ref "J3") (pin "P$103") (pinfunction "A13_P$103") (pintype "passive"))
      (node (ref "J4") (pin "P$103") (pinfunction "A13_P$103") (pintype "passive"))
      (node (ref "J5") (pin "P$103") (pinfunction "A13_P$103") (pintype "passive"))
      (node (ref "J6") (pin "P$103") (pinfunction "A13_P$103") (pintype "passive"))
    )
    (net (code "30") (name "H1-26") (class "Default")
      (node (ref "J1") (pin "P$73") (pinfunction "B13_P$73") (pintype "passive"))
      (node (ref "J2") (pin "P$73") (pinfunction "B13_P$73") (pintype "passive"))
      (node (ref "J3") (pin "P$73") (pinfunction "B13_P$73") (pintype "passive"))
      (node (ref "J4") (pin "P$73") (pinfunction "B13_P$73") (pintype "passive"))
      (node (ref "J5") (pin "P$73") (pinfunction "B13_P$73") (pintype "passive"))
      (node (ref "J6") (pin "P$73") (pinfunction "B13_P$73") (pintype "passive"))
    )
    (net (code "31") (name "H1-27") (class "Default")
      (node (ref "J1") (pin "P$104") (pinfunction "A14_P$104") (pintype "passive"))
      (node (ref "J2") (pin "P$104") (pinfunction "A14_P$104") (pintype "passive"))
      (node (ref "J3") (pin "P$104") (pinfunction "A14_P$104") (pintype "passive"))
      (node (ref "J4") (pin "P$104") (pinfunction "A14_P$104") (pintype "passive"))
      (node (ref "J5") (pin "P$104") (pinfunction "A14_P$104") (pintype "passive"))
      (node (ref "J6") (pin "P$104") (pinfunction "A14_P$104") (pintype "passive"))
    )
    (net (code "32") (name "H1-28") (class "Default")
      (node (ref "J1") (pin "P$74") (pinfunction "B14_P$74") (pintype "passive"))
      (node (ref "J2") (pin "P$74") (pinfunction "B14_P$74") (pintype "passive"))
      (node (ref "J3") (pin "P$74") (pinfunction "B14_P$74") (pintype "passive"))
      (node (ref "J4") (pin "P$74") (pinfunction "B14_P$74") (pintype "passive"))
      (node (ref "J5") (pin "P$74") (pinfunction "B14_P$74") (pintype "passive"))
      (node (ref "J6") (pin "P$74") (pinfunction "B14_P$74") (pintype "passive"))
    )
    (net (code "33") (name "H1-29") (class "Default")
      (node (ref "J1") (pin "P$105") (pinfunction "A15_P$105") (pintype "passive"))
      (node (ref "J2") (pin "P$105") (pinfunction "A15_P$105") (pintype "passive"))
      (node (ref "J3") (pin "P$105") (pinfunction "A15_P$105") (pintype "passive"))
      (node (ref "J4") (pin "P$105") (pinfunction "A15_P$105") (pintype "passive"))
      (node (ref "J5") (pin "P$105") (pinfunction "A15_P$105") (pintype "passive"))
      (node (ref "J6") (pin "P$105") (pinfunction "A15_P$105") (pintype "passive"))
    )
    (net (code "34") (name "H1-30") (class "Default")
      (node (ref "J1") (pin "P$75") (pinfunction "B15_P$75") (pintype "passive"))
      (node (ref "J2") (pin "P$75") (pinfunction "B15_P$75") (pintype "passive"))
      (node (ref "J3") (pin "P$75") (pinfunction "B15_P$75") (pintype "passive"))
      (node (ref "J4") (pin "P$75") (pinfunction "B15_P$75") (pintype "passive"))
      (node (ref "J5") (pin "P$75") (pinfunction "B15_P$75") (pintype "passive"))
      (node (ref "J6") (pin "P$75") (pinfunction "B15_P$75") (pintype "passive"))
    )
    (net (code "35") (name "H1-31") (class "Default")
      (node (ref "J1") (pin "P$106") (pinfunction "A16_P$106") (pintype "passive"))
      (node (ref "J2") (pin "P$106") (pinfunction "A16_P$106") (pintype "passive"))
      (node (ref "J3") (pin "P$106") (pinfunction "A16_P$106") (pintype "passive"))
      (node (ref "J4") (pin "P$106") (pinfunction "A16_P$106") (pintype "passive"))
      (node (ref "J5") (pin "P$106") (pinfunction "A16_P$106") (pintype "passive"))
      (node (ref "J6") (pin "P$106") (pinfunction "A16_P$106") (pintype "passive"))
    )
    (net (code "36") (name "H1-32") (class "Default")
      (node (ref "J1") (pin "P$76") (pinfunction "B16_P$76") (pintype "passive"))
      (node (ref "J2") (pin "P$76") (pinfunction "B16_P$76") (pintype "passive"))
      (node (ref "J3") (pin "P$76") (pinfunction "B16_P$76") (pintype "passive"))
      (node (ref "J4") (pin "P$76") (pinfunction "B16_P$76") (pintype "passive"))
      (node (ref "J5") (pin "P$76") (pinfunction "B16_P$76") (pintype "passive"))
      (node (ref "J6") (pin "P$76") (pinfunction "B16_P$76") (pintype "passive"))
    )
    (net (code "37") (name "H1-33") (class "Default")
      (node (ref "J1") (pin "P$107") (pinfunction "A17_P$107") (pintype "passive"))
      (node (ref "J2") (pin "P$107") (pinfunction "A17_P$107") (pintype "passive"))
      (node (ref "J3") (pin "P$107") (pinfunction "A17_P$107") (pintype "passive"))
      (node (ref "J4") (pin "P$107") (pinfunction "A17_P$107") (pintype "passive"))
      (node (ref "J5") (pin "P$107") (pinfunction "A17_P$107") (pintype "passive"))
      (node (ref "J6") (pin "P$107") (pinfunction "A17_P$107") (pintype "passive"))
    )
    (net (code "38") (name "H1-34") (class "Default")
      (node (ref "J1") (pin "P$77") (pinfunction "B17_P$77") (pintype "passive"))
      (node (ref "J2") (pin "P$77") (pinfunction "B17_P$77") (pintype "passive"))
      (node (ref "J3") (pin "P$77") (pinfunction "B17_P$77") (pintype "passive"))
      (node (ref "J4") (pin "P$77") (pinfunction "B17_P$77") (pintype "passive"))
      (node (ref "J5") (pin "P$77") (pinfunction "B17_P$77") (pintype "passive"))
      (node (ref "J6") (pin "P$77") (pinfunction "B17_P$77") (pintype "passive"))
    )
    (net (code "39") (name "H1-35") (class "Default")
      (node (ref "J1") (pin "P$108") (pinfunction "A18_P$108") (pintype "passive"))
      (node (ref "J2") (pin "P$108") (pinfunction "A18_P$108") (pintype "passive"))
      (node (ref "J3") (pin "P$108") (pinfunction "A18_P$108") (pintype "passive"))
      (node (ref "J4") (pin "P$108") (pinfunction "A18_P$108") (pintype "passive"))
      (node (ref "J5") (pin "P$108") (pinfunction "A18_P$108") (pintype "passive"))
      (node (ref "J6") (pin "P$108") (pinfunction "A18_P$108") (pintype "passive"))
    )
    (net (code "40") (name "H1-36") (class "Default")
      (node (ref "J1") (pin "P$78") (pinfunction "B18_P$78") (pintype "passive"))
      (node (ref "J2") (pin "P$78") (pinfunction "B18_P$78") (pintype "passive"))
      (node (ref "J3") (pin "P$78") (pinfunction "B18_P$78") (pintype "passive"))
      (node (ref "J4") (pin "P$78") (pinfunction "B18_P$78") (pintype "passive"))
      (node (ref "J5") (pin "P$78") (pinfunction "B18_P$78") (pintype "passive"))
      (node (ref "J6") (pin "P$78") (pinfunction "B18_P$78") (pintype "passive"))
    )
    (net (code "41") (name "H1-37") (class "Default")
      (node (ref "J1") (pin "P$109") (pinfunction "A19_P$109") (pintype "passive"))
      (node (ref "J2") (pin "P$109") (pinfunction "A19_P$109") (pintype "passive"))
      (node (ref "J3") (pin "P$109") (pinfunction "A19_P$109") (pintype "passive"))
      (node (ref "J4") (pin "P$109") (pinfunction "A19_P$109") (pintype "passive"))
      (node (ref "J5") (pin "P$109") (pinfunction "A19_P$109") (pintype "passive"))
      (node (ref "J6") (pin "P$109") (pinfunction "A19_P$109") (pintype "passive"))
    )
    (net (code "42") (name "H1-38") (class "Default")
      (node (ref "J1") (pin "P$79") (pinfunction "B19_P$79") (pintype "passive"))
      (node (ref "J2") (pin "P$79") (pinfunction "B19_P$79") (pintype "passive"))
      (node (ref "J3") (pin "P$79") (pinfunction "B19_P$79") (pintype "passive"))
      (node (ref "J4") (pin "P$79") (pinfunction "B19_P$79") (pintype "passive"))
      (node (ref "J5") (pin "P$79") (pinfunction "B19_P$79") (pintype "passive"))
      (node (ref "J6") (pin "P$79") (pinfunction "B19_P$79") (pintype "passive"))
    )
    (net (code "43") (name "H1-39") (class "Default")
      (node (ref "J1") (pin "P$110") (pinfunction "A20_P$110") (pintype "passive"))
      (node (ref "J2") (pin "P$110") (pinfunction "A20_P$110") (pintype "passive"))
      (node (ref "J3") (pin "P$110") (pinfunction "A20_P$110") (pintype "passive"))
      (node (ref "J4") (pin "P$110") (pinfunction "A20_P$110") (pintype "passive"))
      (node (ref "J5") (pin "P$110") (pinfunction "A20_P$110") (pintype "passive"))
      (node (ref "J6") (pin "P$110") (pinfunction "A20_P$110") (pintype "passive"))
    )
    (net (code "44") (name "H1-40") (class "Default")
      (node (ref "J1") (pin "P$80") (pinfunction "B20_P$80") (pintype "passive"))
      (node (ref "J2") (pin "P$80") (pinfunction "B20_P$80") (pintype "passive"))
      (node (ref "J3") (pin "P$80") (pinfunction "B20_P$80") (pintype "passive"))
      (node (ref "J4") (pin "P$80") (pinfunction "B20_P$80") (pintype "passive"))
      (node (ref "J5") (pin "P$80") (pinfunction "B20_P$80") (pintype "passive"))
      (node (ref "J6") (pin "P$80") (pinfunction "B20_P$80") (pintype "passive"))
    )
    (net (code "45") (name "H1-41") (class "Default")
      (node (ref "J1") (pin "P$111") (pinfunction "A21_P$111") (pintype "passive"))
      (node (ref "J2") (pin "P$111") (pinfunction "A21_P$111") (pintype "passive"))
      (node (ref "J3") (pin "P$111") (pinfunction "A21_P$111") (pintype "passive"))
      (node (ref "J4") (pin "P$111") (pinfunction "A21_P$111") (pintype "passive"))
      (node (ref "J5") (pin "P$111") (pinfunction "A21_P$111") (pintype "passive"))
      (node (ref "J6") (pin "P$111") (pinfunction "A21_P$111") (pintype "passive"))
    )
    (net (code "46") (name "H1-42") (class "Default")
      (node (ref "J1") (pin "P$81") (pinfunction "B21_P$81") (pintype "passive"))
      (node (ref "J2") (pin "P$81") (pinfunction "B21_P$81") (pintype "passive"))
      (node (ref "J3") (pin "P$81") (pinfunction "B21_P$81") (pintype "passive"))
      (node (ref "J4") (pin "P$81") (pinfunction "B21_P$81") (pintype "passive"))
      (node (ref "J5") (pin "P$81") (pinfunction "B21_P$81") (pintype "passive"))
      (node (ref "J6") (pin "P$81") (pinfunction "B21_P$81") (pintype "passive"))
    )
    (net (code "47") (name "H1-43") (class "Default")
      (node (ref "J1") (pin "P$112") (pinfunction "A22_P$112") (pintype "passive"))
      (node (ref "J2") (pin "P$112") (pinfunction "A22_P$112") (pintype "passive"))
      (node (ref "J3") (pin "P$112") (pinfunction "A22_P$112") (pintype "passive"))
      (node (ref "J4") (pin "P$112") (pinfunction "A22_P$112") (pintype "passive"))
      (node (ref "J5") (pin "P$112") (pinfunction "A22_P$112") (pintype "passive"))
      (node (ref "J6") (pin "P$112") (pinfunction "A22_P$112") (pintype "passive"))
    )
    (net (code "48") (name "H1-44") (class "Default")
      (node (ref "J1") (pin "P$82") (pinfunction "B22_P$82") (pintype "passive"))
      (node (ref "J2") (pin "P$82") (pinfunction "B22_P$82") (pintype "passive"))
      (node (ref "J3") (pin "P$82") (pinfunction "B22_P$82") (pintype "passive"))
      (node (ref "J4") (pin "P$82") (pinfunction "B22_P$82") (pintype "passive"))
      (node (ref "J5") (pin "P$82") (pinfunction "B22_P$82") (pintype "passive"))
      (node (ref "J6") (pin "P$82") (pinfunction "B22_P$82") (pintype "passive"))
    )
    (net (code "49") (name "H1-45") (class "Default")
      (node (ref "J1") (pin "P$113") (pinfunction "A23_P$113") (pintype "passive"))
      (node (ref "J2") (pin "P$113") (pinfunction "A23_P$113") (pintype "passive"))
      (node (ref "J3") (pin "P$113") (pinfunction "A23_P$113") (pintype "passive"))
      (node (ref "J4") (pin "P$113") (pinfunction "A23_P$113") (pintype "passive"))
      (node (ref "J5") (pin "P$113") (pinfunction "A23_P$113") (pintype "passive"))
      (node (ref "J6") (pin "P$113") (pinfunction "A23_P$113") (pintype "passive"))
    )
    (net (code "50") (name "H1-46") (class "Default")
      (node (ref "J1") (pin "P$83") (pinfunction "B23_P$83") (pintype "passive"))
      (node (ref "J2") (pin "P$83") (pinfunction "B23_P$83") (pintype "passive"))
      (node (ref "J3") (pin "P$83") (pinfunction "B23_P$83") (pintype "passive"))
      (node (ref "J4") (pin "P$83") (pinfunction "B23_P$83") (pintype "passive"))
      (node (ref "J5") (pin "P$83") (pinfunction "B23_P$83") (pintype "passive"))
      (node (ref "J6") (pin "P$83") (pinfunction "B23_P$83") (pintype "passive"))
    )
    (net (code "51") (name "H1-47") (class "Default")
      (node (ref "J1") (pin "P$114") (pinfunction "A24_P$114") (pintype "passive"))
      (node (ref "J2") (pin "P$114") (pinfunction "A24_P$114") (pintype "passive"))
      (node (ref "J3") (pin "P$114") (pinfunction "A24_P$114") (pintype "passive"))
      (node (ref "J4") (pin "P$114") (pinfunction "A24_P$114") (pintype "passive"))
      (node (ref "J5") (pin "P$114") (pinfunction "A24_P$114") (pintype "passive"))
      (node (ref "J6") (pin "P$114") (pinfunction "A24_P$114") (pintype "passive"))
    )
    (net (code "52") (name "H1-48") (class "Default")
      (node (ref "J1") (pin "P$84") (pinfunction "B24_P$84") (pintype "passive"))
      (node (ref "J2") (pin "P$84") (pinfunction "B24_P$84") (pintype "passive"))
      (node (ref "J3") (pin "P$84") (pinfunction "B24_P$84") (pintype "passive"))
      (node (ref "J4") (pin "P$84") (pinfunction "B24_P$84") (pintype "passive"))
      (node (ref "J5") (pin "P$84") (pinfunction "B24_P$84") (pintype "passive"))
      (node (ref "J6") (pin "P$84") (pinfunction "B24_P$84") (pintype "passive"))
    )
    (net (code "53") (name "H1-49") (class "Default")
      (node (ref "J1") (pin "P$115") (pinfunction "A25_P$115") (pintype "passive"))
      (node (ref "J2") (pin "P$115") (pinfunction "A25_P$115") (pintype "passive"))
      (node (ref "J3") (pin "P$115") (pinfunction "A25_P$115") (pintype "passive"))
      (node (ref "J4") (pin "P$115") (pinfunction "A25_P$115") (pintype "passive"))
      (node (ref "J5") (pin "P$115") (pinfunction "A25_P$115") (pintype "passive"))
      (node (ref "J6") (pin "P$115") (pinfunction "A25_P$115") (pintype "passive"))
    )
    (net (code "54") (name "H1-50") (class "Default")
      (node (ref "J1") (pin "P$85") (pinfunction "B25_P$85") (pintype "passive"))
      (node (ref "J2") (pin "P$85") (pinfunction "B25_P$85") (pintype "passive"))
      (node (ref "J3") (pin "P$85") (pinfunction "B25_P$85") (pintype "passive"))
      (node (ref "J4") (pin "P$85") (pinfunction "B25_P$85") (pintype "passive"))
      (node (ref "J5") (pin "P$85") (pinfunction "B25_P$85") (pintype "passive"))
      (node (ref "J6") (pin "P$85") (pinfunction "B25_P$85") (pintype "passive"))
    )
    (net (code "55") (name "H1-51") (class "Default")
      (node (ref "J1") (pin "P$116") (pinfunction "A26_P$116") (pintype "passive"))
      (node (ref "J2") (pin "P$116") (pinfunction "A26_P$116") (pintype "passive"))
      (node (ref "J3") (pin "P$116") (pinfunction "A26_P$116") (pintype "passive"))
      (node (ref "J4") (pin "P$116") (pinfunction "A26_P$116") (pintype "passive"))
      (node (ref "J5") (pin "P$116") (pinfunction "A26_P$116") (pintype "passive"))
      (node (ref "J6") (pin "P$116") (pinfunction "A26_P$116") (pintype "passive"))
    )
    (net (code "56") (name "H1-52") (class "Default")
      (node (ref "J1") (pin "P$86") (pinfunction "B26_P$86") (pintype "passive"))
      (node (ref "J2") (pin "P$86") (pinfunction "B26_P$86") (pintype "passive"))
      (node (ref "J3") (pin "P$86") (pinfunction "B26_P$86") (pintype "passive"))
      (node (ref "J4") (pin "P$86") (pinfunction "B26_P$86") (pintype "passive"))
      (node (ref "J5") (pin "P$86") (pinfunction "B26_P$86") (pintype "passive"))
      (node (ref "J6") (pin "P$86") (pinfunction "B26_P$86") (pintype "passive"))
    )
    (net (code "57") (name "H2-1") (class "Default")
      (node (ref "J1") (pin "P$31") (pinfunction "C1_P$31") (pintype "passive"))
      (node (ref "J2") (pin "P$31") (pinfunction "C1_P$31") (pintype "passive"))
      (node (ref "J3") (pin "P$31") (pinfunction "C1_P$31") (pintype "passive"))
      (node (ref "J4") (pin "P$31") (pinfunction "C1_P$31") (pintype "passive"))
      (node (ref "J5") (pin "P$31") (pinfunction "C1_P$31") (pintype "passive"))
      (node (ref "J6") (pin "P$31") (pinfunction "C1_P$31") (pintype "passive"))
    )
    (net (code "58") (name "H2-2") (class "Default")
      (node (ref "J1") (pin "P$1") (pinfunction "D1_P$1") (pintype "passive"))
      (node (ref "J2") (pin "P$1") (pinfunction "D1_P$1") (pintype "passive"))
      (node (ref "J3") (pin "P$1") (pinfunction "D1_P$1") (pintype "passive"))
      (node (ref "J4") (pin "P$1") (pinfunction "D1_P$1") (pintype "passive"))
      (node (ref "J5") (pin "P$1") (pinfunction "D1_P$1") (pintype "passive"))
      (node (ref "J6") (pin "P$1") (pinfunction "D1_P$1") (pintype "passive"))
    )
    (net (code "59") (name "H2-3") (class "Default")
      (node (ref "J1") (pin "P$32") (pinfunction "C2_P$32") (pintype "passive"))
      (node (ref "J2") (pin "P$32") (pinfunction "C2_P$32") (pintype "passive"))
      (node (ref "J3") (pin "P$32") (pinfunction "C2_P$32") (pintype "passive"))
      (node (ref "J4") (pin "P$32") (pinfunction "C2_P$32") (pintype "passive"))
      (node (ref "J5") (pin "P$32") (pinfunction "C2_P$32") (pintype "passive"))
      (node (ref "J6") (pin "P$32") (pinfunction "C2_P$32") (pintype "passive"))
    )
    (net (code "60") (name "H2-4") (class "Default")
      (node (ref "J1") (pin "P$2") (pinfunction "D2_P$2") (pintype "passive"))
      (node (ref "J2") (pin "P$2") (pinfunction "D2_P$2") (pintype "passive"))
      (node (ref "J3") (pin "P$2") (pinfunction "D2_P$2") (pintype "passive"))
      (node (ref "J4") (pin "P$2") (pinfunction "D2_P$2") (pintype "passive"))
      (node (ref "J5") (pin "P$2") (pinfunction "D2_P$2") (pintype "passive"))
      (node (ref "J6") (pin "P$2") (pinfunction "D2_P$2") (pintype "passive"))
    )
    (net (code "61") (name "H2-5") (class "Default")
      (node (ref "J1") (pin "P$33") (pinfunction "C3_P$33") (pintype "passive"))
      (node (ref "J2") (pin "P$33") (pinfunction "C3_P$33") (pintype "passive"))
      (node (ref "J3") (pin "P$33") (pinfunction "C3_P$33") (pintype "passive"))
      (node (ref "J4") (pin "P$33") (pinfunction "C3_P$33") (pintype "passive"))
      (node (ref "J5") (pin "P$33") (pinfunction "C3_P$33") (pintype "passive"))
      (node (ref "J6") (pin "P$33") (pinfunction "C3_P$33") (pintype "passive"))
    )
    (net (code "62") (name "H2-6") (class "Default")
      (node (ref "J1") (pin "P$3") (pinfunction "D3_P$3") (pintype "passive"))
      (node (ref "J2") (pin "P$3") (pinfunction "D3_P$3") (pintype "passive"))
      (node (ref "J3") (pin "P$3") (pinfunction "D3_P$3") (pintype "passive"))
      (node (ref "J4") (pin "P$3") (pinfunction "D3_P$3") (pintype "passive"))
      (node (ref "J5") (pin "P$3") (pinfunction "D3_P$3") (pintype "passive"))
      (node (ref "J6") (pin "P$3") (pinfunction "D3_P$3") (pintype "passive"))
    )
    (net (code "63") (name "H2-7") (class "Default")
      (node (ref "J1") (pin "P$34") (pinfunction "C4_P$34") (pintype "passive"))
      (node (ref "J2") (pin "P$34") (pinfunction "C4_P$34") (pintype "passive"))
      (node (ref "J3") (pin "P$34") (pinfunction "C4_P$34") (pintype "passive"))
      (node (ref "J4") (pin "P$34") (pinfunction "C4_P$34") (pintype "passive"))
      (node (ref "J5") (pin "P$34") (pinfunction "C4_P$34") (pintype "passive"))
      (node (ref "J6") (pin "P$34") (pinfunction "C4_P$34") (pintype "passive"))
    )
    (net (code "64") (name "H2-8") (class "Default")
      (node (ref "J1") (pin "P$4") (pinfunction "D4_P$4") (pintype "passive"))
      (node (ref "J2") (pin "P$4") (pinfunction "D4_P$4") (pintype "passive"))
      (node (ref "J3") (pin "P$4") (pinfunction "D4_P$4") (pintype "passive"))
      (node (ref "J4") (pin "P$4") (pinfunction "D4_P$4") (pintype "passive"))
      (node (ref "J5") (pin "P$4") (pinfunction "D4_P$4") (pintype "passive"))
      (node (ref "J6") (pin "P$4") (pinfunction "D4_P$4") (pintype "passive"))
    )
    (net (code "65") (name "H2-10") (class "Default")
      (node (ref "J1") (pin "P$5") (pinfunction "D5_P$5") (pintype "passive"))
      (node (ref "J2") (pin "P$5") (pinfunction "D5_P$5") (pintype "passive"))
      (node (ref "J3") (pin "P$5") (pinfunction "D5_P$5") (pintype "passive"))
      (node (ref "J4") (pin "P$5") (pinfunction "D5_P$5") (pintype "passive"))
      (node (ref "J5") (pin "P$5") (pinfunction "D5_P$5") (pintype "passive"))
      (node (ref "J6") (pin "P$5") (pinfunction "D5_P$5") (pintype "passive"))
    )
    (net (code "66") (name "H2-11") (class "Default")
      (node (ref "J1") (pin "P$36") (pinfunction "C6_P$36") (pintype "passive"))
      (node (ref "J2") (pin "P$36") (pinfunction "C6_P$36") (pintype "passive"))
      (node (ref "J3") (pin "P$36") (pinfunction "C6_P$36") (pintype "passive"))
      (node (ref "J4") (pin "P$36") (pinfunction "C6_P$36") (pintype "passive"))
      (node (ref "J5") (pin "P$36") (pinfunction "C6_P$36") (pintype "passive"))
      (node (ref "J6") (pin "P$36") (pinfunction "C6_P$36") (pintype "passive"))
    )
    (net (code "67") (name "H2-12") (class "Default")
      (node (ref "J1") (pin "P$6") (pinfunction "D6_P$6") (pintype "passive"))
      (node (ref "J2") (pin "P$6") (pinfunction "D6_P$6") (pintype "passive"))
      (node (ref "J3") (pin "P$6") (pinfunction "D6_P$6") (pintype "passive"))
      (node (ref "J4") (pin "P$6") (pinfunction "D6_P$6") (pintype "passive"))
      (node (ref "J5") (pin "P$6") (pinfunction "D6_P$6") (pintype "passive"))
      (node (ref "J6") (pin "P$6") (pinfunction "D6_P$6") (pintype "passive"))
    )
    (net (code "68") (name "H2-13") (class "Default")
      (node (ref "J1") (pin "P$37") (pinfunction "C7_P$37") (pintype "passive"))
      (node (ref "J2") (pin "P$37") (pinfunction "C7_P$37") (pintype "passive"))
      (node (ref "J3") (pin "P$37") (pinfunction "C7_P$37") (pintype "passive"))
      (node (ref "J4") (pin "P$37") (pinfunction "C7_P$37") (pintype "passive"))
      (node (ref "J5") (pin "P$37") (pinfunction "C7_P$37") (pintype "passive"))
      (node (ref "J6") (pin "P$37") (pinfunction "C7_P$37") (pintype "passive"))
    )
    (net (code "69") (name "H2-15") (class "Default")
      (node (ref "J1") (pin "P$38") (pinfunction "C8_P$38") (pintype "passive"))
      (node (ref "J2") (pin "P$38") (pinfunction "C8_P$38") (pintype "passive"))
      (node (ref "J3") (pin "P$38") (pinfunction "C8_P$38") (pintype "passive"))
      (node (ref "J4") (pin "P$38") (pinfunction "C8_P$38") (pintype "passive"))
      (node (ref "J5") (pin "P$38") (pinfunction "C8_P$38") (pintype "passive"))
      (node (ref "J6") (pin "P$38") (pinfunction "C8_P$38") (pintype "passive"))
    )
    (net (code "70") (name "H2-16") (class "Default")
      (node (ref "J1") (pin "P$8") (pinfunction "D8_P$8") (pintype "passive"))
      (node (ref "J2") (pin "P$8") (pinfunction "D8_P$8") (pintype "passive"))
      (node (ref "J3") (pin "P$8") (pinfunction "D8_P$8") (pintype "passive"))
      (node (ref "J4") (pin "P$8") (pinfunction "D8_P$8") (pintype "passive"))
      (node (ref "J5") (pin "P$8") (pinfunction "D8_P$8") (pintype "passive"))
      (node (ref "J6") (pin "P$8") (pinfunction "D8_P$8") (pintype "passive"))
    )
    (net (code "71") (name "H2-18") (class "Default")
      (node (ref "J1") (pin "P$9") (pinfunction "D9_P$9") (pintype "passive"))
      (node (ref "J2") (pin "P$9") (pinfunction "D9_P$9") (pintype "passive"))
      (node (ref "J3") (pin "P$9") (pinfunction "D9_P$9") (pintype "passive"))
      (node (ref "J4") (pin "P$9") (pinfunction "D9_P$9") (pintype "passive"))
      (node (ref "J5") (pin "P$9") (pinfunction "D9_P$9") (pintype "passive"))
      (node (ref "J6") (pin "P$9") (pinfunction "D9_P$9") (pintype "passive"))
    )
    (net (code "72") (name "H2-19") (class "Default")
      (node (ref "J1") (pin "P$40") (pinfunction "C10_P$40") (pintype "passive"))
      (node (ref "J2") (pin "P$40") (pinfunction "C10_P$40") (pintype "passive"))
      (node (ref "J3") (pin "P$40") (pinfunction "C10_P$40") (pintype "passive"))
      (node (ref "J4") (pin "P$40") (pinfunction "C10_P$40") (pintype "passive"))
      (node (ref "J5") (pin "P$40") (pinfunction "C10_P$40") (pintype "passive"))
      (node (ref "J6") (pin "P$40") (pinfunction "C10_P$40") (pintype "passive"))
    )
    (net (code "73") (name "H2-20") (class "Default")
      (node (ref "J1") (pin "P$10") (pinfunction "D10_P$10") (pintype "passive"))
      (node (ref "J2") (pin "P$10") (pinfunction "D10_P$10") (pintype "passive"))
      (node (ref "J3") (pin "P$10") (pinfunction "D10_P$10") (pintype "passive"))
      (node (ref "J4") (pin "P$10") (pinfunction "D10_P$10") (pintype "passive"))
      (node (ref "J5") (pin "P$10") (pinfunction "D10_P$10") (pintype "passive"))
      (node (ref "J6") (pin "P$10") (pinfunction "D10_P$10") (pintype "passive"))
    )
    (net (code "74") (name "H2-31") (class "Default")
      (node (ref "J1") (pin "P$46") (pinfunction "C16_P$46") (pintype "passive"))
      (node (ref "J2") (pin "P$46") (pinfunction "C16_P$46") (pintype "passive"))
      (node (ref "J3") (pin "P$46") (pinfunction "C16_P$46") (pintype "passive"))
      (node (ref "J4") (pin "P$46") (pinfunction "C16_P$46") (pintype "passive"))
      (node (ref "J5") (pin "P$46") (pinfunction "C16_P$46") (pintype "passive"))
      (node (ref "J6") (pin "P$46") (pinfunction "C16_P$46") (pintype "passive"))
    )
    (net (code "75") (name "H2-33") (class "Default")
      (node (ref "J1") (pin "P$47") (pinfunction "C17_P$47") (pintype "passive"))
      (node (ref "J2") (pin "P$47") (pinfunction "C17_P$47") (pintype "passive"))
      (node (ref "J3") (pin "P$47") (pinfunction "C17_P$47") (pintype "passive"))
      (node (ref "J4") (pin "P$47") (pinfunction "C17_P$47") (pintype "passive"))
      (node (ref "J5") (pin "P$47") (pinfunction "C17_P$47") (pintype "passive"))
      (node (ref "J6") (pin "P$47") (pinfunction "C17_P$47") (pintype "passive"))
    )
    (net (code "76") (name "H2-34") (class "Default")
      (node (ref "J1") (pin "P$17") (pinfunction "D17_P$17") (pintype "passive"))
      (node (ref "J2") (pin "P$17") (pinfunction "D17_P$17") (pintype "passive"))
      (node (ref "J3") (pin "P$17") (pinfunction "D17_P$17") (pintype "passive"))
      (node (ref "J4") (pin "P$17") (pinfunction "D17_P$17") (pintype "passive"))
      (node (ref "J5") (pin "P$17") (pinfunction "D17_P$17") (pintype "passive"))
      (node (ref "J6") (pin "P$17") (pinfunction "D17_P$17") (pintype "passive"))
    )
    (net (code "77") (name "H2-35") (class "Default")
      (node (ref "J1") (pin "P$48") (pinfunction "C18_P$48") (pintype "passive"))
      (node (ref "J2") (pin "P$48") (pinfunction "C18_P$48") (pintype "passive"))
      (node (ref "J3") (pin "P$48") (pinfunction "C18_P$48") (pintype "passive"))
      (node (ref "J4") (pin "P$48") (pinfunction "C18_P$48") (pintype "passive"))
      (node (ref "J5") (pin "P$48") (pinfunction "C18_P$48") (pintype "passive"))
      (node (ref "J6") (pin "P$48") (pinfunction "C18_P$48") (pintype "passive"))
    )
    (net (code "78") (name "H2-36") (class "Default")
      (node (ref "J1") (pin "P$18") (pinfunction "D18_P$18") (pintype "passive"))
      (node (ref "J2") (pin "P$18") (pinfunction "D18_P$18") (pintype "passive"))
      (node (ref "J3") (pin "P$18") (pinfunction "D18_P$18") (pintype "passive"))
      (node (ref "J4") (pin "P$18") (pinfunction "D18_P$18") (pintype "passive"))
      (node (ref "J5") (pin "P$18") (pinfunction "D18_P$18") (pintype "passive"))
      (node (ref "J6") (pin "P$18") (pinfunction "D18_P$18") (pintype "passive"))
    )
    (net (code "79") (name "H2-37") (class "Default")
      (node (ref "J1") (pin "P$49") (pinfunction "C19_P$49") (pintype "passive"))
      (node (ref "J2") (pin "P$49") (pinfunction "C19_P$49") (pintype "passive"))
      (node (ref "J3") (pin "P$49") (pinfunction "C19_P$49") (pintype "passive"))
      (node (ref "J4") (pin "P$49") (pinfunction "C19_P$49") (pintype "passive"))
      (node (ref "J5") (pin "P$49") (pinfunction "C19_P$49") (pintype "passive"))
      (node (ref "J6") (pin "P$49") (pinfunction "C19_P$49") (pintype "passive"))
    )
    (net (code "80") (name "H2-38") (class "Default")
      (node (ref "J1") (pin "P$19") (pinfunction "D19_P$19") (pintype "passive"))
      (node (ref "J2") (pin "P$19") (pinfunction "D19_P$19") (pintype "passive"))
      (node (ref "J3") (pin "P$19") (pinfunction "D19_P$19") (pintype "passive"))
      (node (ref "J4") (pin "P$19") (pinfunction "D19_P$19") (pintype "passive"))
      (node (ref "J5") (pin "P$19") (pinfunction "D19_P$19") (pintype "passive"))
      (node (ref "J6") (pin "P$19") (pinfunction "D19_P$19") (pintype "passive"))
    )
    (net (code "81") (name "H2-39") (class "Default")
      (node (ref "J1") (pin "P$50") (pinfunction "C20_P$50") (pintype "passive"))
      (node (ref "J2") (pin "P$50") (pinfunction "C20_P$50") (pintype "passive"))
      (node (ref "J3") (pin "P$50") (pinfunction "C20_P$50") (pintype "passive"))
      (node (ref "J4") (pin "P$50") (pinfunction "C20_P$50") (pintype "passive"))
      (node (ref "J5") (pin "P$50") (pinfunction "C20_P$50") (pintype "passive"))
      (node (ref "J6") (pin "P$50") (pinfunction "C20_P$50") (pintype "passive"))
    )
    (net (code "82") (name "H2-40") (class "Default")
      (node (ref "J1") (pin "P$20") (pinfunction "D20_P$20") (pintype "passive"))
      (node (ref "J2") (pin "P$20") (pinfunction "D20_P$20") (pintype "passive"))
      (node (ref "J3") (pin "P$20") (pinfunction "D20_P$20") (pintype "passive"))
      (node (ref "J4") (pin "P$20") (pinfunction "D20_P$20") (pintype "passive"))
      (node (ref "J5") (pin "P$20") (pinfunction "D20_P$20") (pintype "passive"))
      (node (ref "J6") (pin "P$20") (pinfunction "D20_P$20") (pintype "passive"))
    )
    (net (code "83") (name "H2-41") (class "Default")
      (node (ref "J1") (pin "P$51") (pinfunction "C21_P$51") (pintype "passive"))
      (node (ref "J2") (pin "P$51") (pinfunction "C21_P$51") (pintype "passive"))
      (node (ref "J3") (pin "P$51") (pinfunction "C21_P$51") (pintype "passive"))
      (node (ref "J4") (pin "P$51") (pinfunction "C21_P$51") (pintype "passive"))
      (node (ref "J5") (pin "P$51") (pinfunction "C21_P$51") (pintype "passive"))
      (node (ref "J6") (pin "P$51") (pinfunction "C21_P$51") (pintype "passive"))
    )
    (net (code "84") (name "H2-42") (class "Default")
      (node (ref "J1") (pin "P$21") (pinfunction "D21_P$21") (pintype "passive"))
      (node (ref "J2") (pin "P$21") (pinfunction "D21_P$21") (pintype "passive"))
      (node (ref "J3") (pin "P$21") (pinfunction "D21_P$21") (pintype "passive"))
      (node (ref "J4") (pin "P$21") (pinfunction "D21_P$21") (pintype "passive"))
      (node (ref "J5") (pin "P$21") (pinfunction "D21_P$21") (pintype "passive"))
      (node (ref "J6") (pin "P$21") (pinfunction "D21_P$21") (pintype "passive"))
    )
    (net (code "85") (name "H2-43") (class "Default")
      (node (ref "J1") (pin "P$52") (pinfunction "C22_P$52") (pintype "passive"))
      (node (ref "J2") (pin "P$52") (pinfunction "C22_P$52") (pintype "passive"))
      (node (ref "J3") (pin "P$52") (pinfunction "C22_P$52") (pintype "passive"))
      (node (ref "J4") (pin "P$52") (pinfunction "C22_P$52") (pintype "passive"))
      (node (ref "J5") (pin "P$52") (pinfunction "C22_P$52") (pintype "passive"))
      (node (ref "J6") (pin "P$52") (pinfunction "C22_P$52") (pintype "passive"))
    )
    (net (code "86") (name "H2-44") (class "Default")
      (node (ref "J1") (pin "P$22") (pinfunction "D22_P$22") (pintype "passive"))
      (node (ref "J2") (pin "P$22") (pinfunction "D22_P$22") (pintype "passive"))
      (node (ref "J3") (pin "P$22") (pinfunction "D22_P$22") (pintype "passive"))
      (node (ref "J4") (pin "P$22") (pinfunction "D22_P$22") (pintype "passive"))
      (node (ref "J5") (pin "P$22") (pinfunction "D22_P$22") (pintype "passive"))
      (node (ref "J6") (pin "P$22") (pinfunction "D22_P$22") (pintype "passive"))
    )
    (net (code "87") (name "H2-49") (class "Default")
      (node (ref "J1") (pin "P$55") (pinfunction "C25_P$55") (pintype "passive"))
      (node (ref "J2") (pin "P$55") (pinfunction "C25_P$55") (pintype "passive"))
      (node (ref "J3") (pin "P$55") (pinfunction "C25_P$55") (pintype "passive"))
      (node (ref "J4") (pin "P$55") (pinfunction "C25_P$55") (pintype "passive"))
      (node (ref "J5") (pin "P$55") (pinfunction "C25_P$55") (pintype "passive"))
      (node (ref "J6") (pin "P$55") (pinfunction "C25_P$55") (pintype "passive"))
    )
    (net (code "88") (name "H2-50") (class "Default")
      (node (ref "J1") (pin "P$25") (pinfunction "D25_P$25") (pintype "passive"))
      (node (ref "J2") (pin "P$25") (pinfunction "D25_P$25") (pintype "passive"))
      (node (ref "J3") (pin "P$25") (pinfunction "D25_P$25") (pintype "passive"))
      (node (ref "J4") (pin "P$25") (pinfunction "D25_P$25") (pintype "passive"))
      (node (ref "J5") (pin "P$25") (pinfunction "D25_P$25") (pintype "passive"))
      (node (ref "J6") (pin "P$25") (pinfunction "D25_P$25") (pintype "passive"))
    )
    (net (code "89") (name "H2-51") (class "Default")
      (node (ref "J1") (pin "P$56") (pinfunction "C26_P$56") (pintype "passive"))
      (node (ref "J2") (pin "P$56") (pinfunction "C26_P$56") (pintype "passive"))
      (node (ref "J3") (pin "P$56") (pinfunction "C26_P$56") (pintype "passive"))
      (node (ref "J4") (pin "P$56") (pinfunction "C26_P$56") (pintype "passive"))
      (node (ref "J5") (pin "P$56") (pinfunction "C26_P$56") (pintype "passive"))
      (node (ref "J6") (pin "P$56") (pinfunction "C26_P$56") (pintype "passive"))
    )
    (net (code "90") (name "H2-52") (class "Default")
      (node (ref "J1") (pin "P$26") (pinfunction "D26_P$26") (pintype "passive"))
      (node (ref "J2") (pin "P$26") (pinfunction "D26_P$26") (pintype "passive"))
      (node (ref "J3") (pin "P$26") (pinfunction "D26_P$26") (pintype "passive"))
      (node (ref "J4") (pin "P$26") (pinfunction "D26_P$26") (pintype "passive"))
      (node (ref "J5") (pin "P$26") (pinfunction "D26_P$26") (pintype "passive"))
      (node (ref "J6") (pin "P$26") (pinfunction "D26_P$26") (pintype "passive"))
    )
    (net (code "91") (name "UN01") (class "Default")
      (node (ref "J1") (pin "P$117") (pinfunction "A27_P$117") (pintype "passive"))
      (node (ref "J2") (pin "P$117") (pinfunction "A27_P$117") (pintype "passive"))
      (node (ref "J3") (pin "P$117") (pinfunction "A27_P$117") (pintype "passive"))
      (node (ref "J4") (pin "P$117") (pinfunction "A27_P$117") (pintype "passive"))
      (node (ref "J5") (pin "P$117") (pinfunction "A27_P$117") (pintype "passive"))
      (node (ref "J6") (pin "P$117") (pinfunction "A27_P$117") (pintype "passive"))
    )
    (net (code "92") (name "UN02") (class "Default")
      (node (ref "J1") (pin "P$87") (pinfunction "B27_P$87") (pintype "passive"))
      (node (ref "J2") (pin "P$87") (pinfunction "B27_P$87") (pintype "passive"))
      (node (ref "J3") (pin "P$87") (pinfunction "B27_P$87") (pintype "passive"))
      (node (ref "J4") (pin "P$87") (pinfunction "B27_P$87") (pintype "passive"))
      (node (ref "J5") (pin "P$87") (pinfunction "B27_P$87") (pintype "passive"))
      (node (ref "J6") (pin "P$87") (pinfunction "B27_P$87") (pintype "passive"))
    )
    (net (code "93") (name "UN03") (class "Default")
      (node (ref "J1") (pin "P$118") (pinfunction "A28_P$118") (pintype "passive"))
      (node (ref "J2") (pin "P$118") (pinfunction "A28_P$118") (pintype "passive"))
      (node (ref "J3") (pin "P$118") (pinfunction "A28_P$118") (pintype "passive"))
      (node (ref "J4") (pin "P$118") (pinfunction "A28_P$118") (pintype "passive"))
      (node (ref "J5") (pin "P$118") (pinfunction "A28_P$118") (pintype "passive"))
      (node (ref "J6") (pin "P$118") (pinfunction "A28_P$118") (pintype "passive"))
    )
    (net (code "94") (name "UN04") (class "Default")
      (node (ref "J1") (pin "P$88") (pinfunction "B28_P$88") (pintype "passive"))
      (node (ref "J2") (pin "P$88") (pinfunction "B28_P$88") (pintype "passive"))
      (node (ref "J3") (pin "P$88") (pinfunction "B28_P$88") (pintype "passive"))
      (node (ref "J4") (pin "P$88") (pinfunction "B28_P$88") (pintype "passive"))
      (node (ref "J5") (pin "P$88") (pinfunction "B28_P$88") (pintype "passive"))
      (node (ref "J6") (pin "P$88") (pinfunction "B28_P$88") (pintype "passive"))
    )
    (net (code "95") (name "UN05") (class "Default")
      (node (ref "J1") (pin "P$119") (pinfunction "A29_P$119") (pintype "passive"))
      (node (ref "J2") (pin "P$119") (pinfunction "A29_P$119") (pintype "passive"))
      (node (ref "J3") (pin "P$119") (pinfunction "A29_P$119") (pintype "passive"))
      (node (ref "J4") (pin "P$119") (pinfunction "A29_P$119") (pintype "passive"))
      (node (ref "J5") (pin "P$119") (pinfunction "A29_P$119") (pintype "passive"))
      (node (ref "J6") (pin "P$119") (pinfunction "A29_P$119") (pintype "passive"))
    )
    (net (code "96") (name "UN06") (class "Default")
      (node (ref "J1") (pin "P$89") (pinfunction "B29_P$89") (pintype "passive"))
      (node (ref "J2") (pin "P$89") (pinfunction "B29_P$89") (pintype "passive"))
      (node (ref "J3") (pin "P$89") (pinfunction "B29_P$89") (pintype "passive"))
      (node (ref "J4") (pin "P$89") (pinfunction "B29_P$89") (pintype "passive"))
      (node (ref "J5") (pin "P$89") (pinfunction "B29_P$89") (pintype "passive"))
      (node (ref "J6") (pin "P$89") (pinfunction "B29_P$89") (pintype "passive"))
    )
    (net (code "97") (name "UN07") (class "Default")
      (node (ref "J1") (pin "P$120") (pinfunction "A30_P$120") (pintype "passive"))
      (node (ref "J2") (pin "P$120") (pinfunction "A30_P$120") (pintype "passive"))
      (node (ref "J3") (pin "P$120") (pinfunction "A30_P$120") (pintype "passive"))
      (node (ref "J4") (pin "P$120") (pinfunction "A30_P$120") (pintype "passive"))
      (node (ref "J5") (pin "P$120") (pinfunction "A30_P$120") (pintype "passive"))
      (node (ref "J6") (pin "P$120") (pinfunction "A30_P$120") (pintype "passive"))
    )
    (net (code "98") (name "UN08") (class "Default")
      (node (ref "J1") (pin "P$90") (pinfunction "B30_P$90") (pintype "passive"))
      (node (ref "J2") (pin "P$90") (pinfunction "B30_P$90") (pintype "passive"))
      (node (ref "J3") (pin "P$90") (pinfunction "B30_P$90") (pintype "passive"))
      (node (ref "J4") (pin "P$90") (pinfunction "B30_P$90") (pintype "passive"))
      (node (ref "J5") (pin "P$90") (pinfunction "B30_P$90") (pintype "passive"))
      (node (ref "J6") (pin "P$90") (pinfunction "B30_P$90") (pintype "passive"))
    )
    (net (code "99") (name "UN09") (class "Default")
      (node (ref "J1") (pin "P$57") (pinfunction "C27_P$57") (pintype "passive"))
      (node (ref "J2") (pin "P$57") (pinfunction "C27_P$57") (pintype "passive"))
      (node (ref "J3") (pin "P$57") (pinfunction "C27_P$57") (pintype "passive"))
      (node (ref "J4") (pin "P$57") (pinfunction "C27_P$57") (pintype "passive"))
      (node (ref "J5") (pin "P$57") (pinfunction "C27_P$57") (pintype "passive"))
      (node (ref "J6") (pin "P$57") (pinfunction "C27_P$57") (pintype "passive"))
    )
    (net (code "100") (name "UN10") (class "Default")
      (node (ref "J1") (pin "P$27") (pinfunction "D27_P$27") (pintype "passive"))
      (node (ref "J2") (pin "P$27") (pinfunction "D27_P$27") (pintype "passive"))
      (node (ref "J3") (pin "P$27") (pinfunction "D27_P$27") (pintype "passive"))
      (node (ref "J4") (pin "P$27") (pinfunction "D27_P$27") (pintype "passive"))
      (node (ref "J5") (pin "P$27") (pinfunction "D27_P$27") (pintype "passive"))
      (node (ref "J6") (pin "P$27") (pinfunction "D27_P$27") (pintype "passive"))
    )
    (net (code "101") (name "UN11") (class "Default")
      (node (ref "J1") (pin "P$58") (pinfunction "C28_P$58") (pintype "passive"))
      (node (ref "J2") (pin "P$58") (pinfunction "C28_P$58") (pintype "passive"))
      (node (ref "J3") (pin "P$58") (pinfunction "C28_P$58") (pintype "passive"))
      (node (ref "J4") (pin "P$58") (pinfunction "C28_P$58") (pintype "passive"))
      (node (ref "J5") (pin "P$58") (pinfunction "C28_P$58") (pintype "passive"))
      (node (ref "J6") (pin "P$58") (pinfunction "C28_P$58") (pintype "passive"))
    )
    (net (code "102") (name "UN12") (class "Default")
      (node (ref "J1") (pin "P$28") (pinfunction "D28_P$28") (pintype "passive"))
      (node (ref "J2") (pin "P$28") (pinfunction "D28_P$28") (pintype "passive"))
      (node (ref "J3") (pin "P$28") (pinfunction "D28_P$28") (pintype "passive"))
      (node (ref "J4") (pin "P$28") (pinfunction "D28_P$28") (pintype "passive"))
      (node (ref "J5") (pin "P$28") (pinfunction "D28_P$28") (pintype "passive"))
      (node (ref "J6") (pin "P$28") (pinfunction "D28_P$28") (pintype "passive"))
    )
    (net (code "103") (name "UN13") (class "Default")
      (node (ref "J1") (pin "P$59") (pinfunction "C29_P$59") (pintype "passive"))
      (node (ref "J2") (pin "P$59") (pinfunction "C29_P$59") (pintype "passive"))
      (node (ref "J3") (pin "P$59") (pinfunction "C29_P$59") (pintype "passive"))
      (node (ref "J4") (pin "P$59") (pinfunction "C29_P$59") (pintype "passive"))
      (node (ref "J5") (pin "P$59") (pinfunction "C29_P$59") (pintype "passive"))
      (node (ref "J6") (pin "P$59") (pinfunction "C29_P$59") (pintype "passive"))
    )
    (net (code "104") (name "UN14") (class "Default")
      (node (ref "J1") (pin "P$29") (pinfunction "D29_P$29") (pintype "passive"))
      (node (ref "J2") (pin "P$29") (pinfunction "D29_P$29") (pintype "passive"))
      (node (ref "J3") (pin "P$29") (pinfunction "D29_P$29") (pintype "passive"))
      (node (ref "J4") (pin "P$29") (pinfunction "D29_P$29") (pintype "passive"))
      (node (ref "J5") (pin "P$29") (pinfunction "D29_P$29") (pintype "passive"))
      (node (ref "J6") (pin "P$29") (pinfunction "D29_P$29") (pintype "passive"))
    )
    (net (code "105") (name "UN15") (class "Default")
      (node (ref "J1") (pin "P$60") (pinfunction "C30_P$60") (pintype "passive"))
      (node (ref "J2") (pin "P$60") (pinfunction "C30_P$60") (pintype "passive"))
      (node (ref "J3") (pin "P$60") (pinfunction "C30_P$60") (pintype "passive"))
      (node (ref "J4") (pin "P$60") (pinfunction "C30_P$60") (pintype "passive"))
      (node (ref "J5") (pin "P$60") (pinfunction "C30_P$60") (pintype "passive"))
      (node (ref "J6") (pin "P$60") (pinfunction "C30_P$60") (pintype "passive"))
    )
    (net (code "106") (name "UN16") (class "Default")
      (node (ref "J1") (pin "P$30") (pinfunction "D30_P$30") (pintype "passive"))
      (node (ref "J2") (pin "P$30") (pinfunction "D30_P$30") (pintype "passive"))
      (node (ref "J3") (pin "P$30") (pinfunction "D30_P$30") (pintype "passive"))
      (node (ref "J4") (pin "P$30") (pinfunction "D30_P$30") (pintype "passive"))
      (node (ref "J5") (pin "P$30") (pinfunction "D30_P$30") (pintype "passive"))
      (node (ref "J6") (pin "P$30") (pinfunction "D30_P$30") (pintype "passive"))
    )
    (net (code "107") (name "VBAT") (class "Default")
      (node (ref "J1") (pin "P$23") (pinfunction "D23_P$23") (pintype "passive"))
      (node (ref "J1") (pin "P$53") (pinfunction "C23_P$53") (pintype "passive"))
      (node (ref "J2") (pin "P$23") (pinfunction "D23_P$23") (pintype "passive"))
      (node (ref "J2") (pin "P$53") (pinfunction "C23_P$53") (pintype "passive"))
      (node (ref "J3") (pin "P$23") (pinfunction "D23_P$23") (pintype "passive"))
      (node (ref "J3") (pin "P$53") (pinfunction "C23_P$53") (pintype "passive"))
      (node (ref "J4") (pin "P$23") (pinfunction "D23_P$23") (pintype "passive"))
      (node (ref "J4") (pin "P$53") (pinfunction "C23_P$53") (pintype "passive"))
      (node (ref "U$6") (pin "P$1") (pinfunction "PIN_P$1") (pintype "bidirectional"))
    )
    (net (code "108") (name "unconnected-(H1-MOUNT-PadB3,2)") (class "Default")
      (node (ref "H1") (pin "B3,2") (pinfunction "MOUNT_B3,2") (pintype "passive"))
    )
    (net (code "109") (name "unconnected-(H2-MOUNT-PadB3,2)") (class "Default")
      (node (ref "H2") (pin "B3,2") (pinfunction "MOUNT_B3,2") (pintype "passive"))
    )
    (net (code "110") (name "unconnected-(H3-MOUNT-PadB3,2)") (class "Default")
      (node (ref "H3") (pin "B3,2") (pinfunction "MOUNT_B3,2") (pintype "passive"))
    )
    (net (code "111") (name "unconnected-(H4-MOUNT-PadB3,2)") (class "Default")
      (node (ref "H4") (pin "B3,2") (pinfunction "MOUNT_B3,2") (pintype "passive"))
    )
    (net (code "112") (name "unconnected-(H5-MOUNT-PadB3,2)") (class "Default")
      (node (ref "H5") (pin "B3,2") (pinfunction "MOUNT_B3,2") (pintype "passive"))
    )
    (net (code "113") (name "unconnected-(H6-MOUNT-PadB3,2)") (class "Default")
      (node (ref "H6") (pin "B3,2") (pinfunction "MOUNT_B3,2") (pintype "passive"))
    )
    (net (code "114") (name "unconnected-(H7-MOUNT-PadB3,2)") (class "Default")
      (node (ref "H7") (pin "B3,2") (pinfunction "MOUNT_B3,2") (pintype "passive"))
    )
    (net (code "115") (name "unconnected-(H8-MOUNT-PadB3,2)") (class "Default")
      (node (ref "H8") (pin "B3,2") (pinfunction "MOUNT_B3,2") (pintype "passive"))
    )
    (net (code "116") (name "unconnected-(H9-MOUNT-PadB3,2)") (class "Default")
      (node (ref "H9") (pin "B3,2") (pinfunction "MOUNT_B3,2") (pintype "passive"))
    )
    (net (code "117") (name "unconnected-(H10-MOUNT-PadB3,2)") (class "Default")
      (node (ref "H10") (pin "B3,2") (pinfunction "MOUNT_B3,2") (pintype "passive"))
    )
    (net (code "118") (name "unconnected-(H11-MOUNT-PadB3,2)") (class "Default")
      (node (ref "H11") (pin "B3,2") (pinfunction "MOUNT_B3,2") (pintype "passive"))
    )
    (net (code "119") (name "unconnected-(H12-MOUNT-PadB3,2)") (class "Default")
      (node (ref "H12") (pin "B3,2") (pinfunction "MOUNT_B3,2") (pintype "passive"))
    )
    (net (code "120") (name "unconnected-(H13-MOUNT-PadB3,2)") (class "Default")
      (node (ref "H13") (pin "B3,2") (pinfunction "MOUNT_B3,2") (pintype "passive"))
    )
    (net (code "121") (name "unconnected-(H14-MOUNT-PadB3,2)") (class "Default")
      (node (ref "H14") (pin "B3,2") (pinfunction "MOUNT_B3,2") (pintype "passive"))
    )
    (net (code "122") (name "unconnected-(H15-MOUNT-PadB3,2)") (class "Default")
      (node (ref "H15") (pin "B3,2") (pinfunction "MOUNT_B3,2") (pintype "passive"))
    )
    (net (code "123") (name "unconnected-(H16-MOUNT-PadB3,2)") (class "Default")
      (node (ref "H16") (pin "B3,2") (pinfunction "MOUNT_B3,2") (pintype "passive"))
    )
    (net (code "124") (name "unconnected-(H17-MOUNT-PadB3,2)") (class "Default")
      (node (ref "H17") (pin "B3,2") (pinfunction "MOUNT_B3,2") (pintype "passive"))
    )
    (net (code "125") (name "unconnected-(H18-MOUNT-PadB3,2)") (class "Default")
      (node (ref "H18") (pin "B3,2") (pinfunction "MOUNT_B3,2") (pintype "passive"))
    )
    (net (code "126") (name "unconnected-(H19-MOUNT-PadB3,2)") (class "Default")
      (node (ref "H19") (pin "B3,2") (pinfunction "MOUNT_B3,2") (pintype "passive"))
    )
    (net (code "127") (name "unconnected-(H20-MOUNT-PadB3,2)") (class "Default")
      (node (ref "H20") (pin "B3,2") (pinfunction "MOUNT_B3,2") (pintype "passive"))
    )
    (net (code "128") (name "unconnected-(H21-MOUNT-PadB3,2)") (class "Default")
      (node (ref "H21") (pin "B3,2") (pinfunction "MOUNT_B3,2") (pintype "passive"))
    )
    (net (code "129") (name "unconnected-(H22-MOUNT-PadB3,2)") (class "Default")
      (node (ref "H22") (pin "B3,2") (pinfunction "MOUNT_B3,2") (pintype "passive"))
    )
    (net (code "130") (name "unconnected-(J5-C12-PadP$42)") (class "Default")
      (node (ref "J5") (pin "P$42") (pinfunction "C12_P$42") (pintype "passive"))
    )
    (net (code "131") (name "unconnected-(J5-C13-PadP$43)") (class "Default")
      (node (ref "J5") (pin "P$43") (pinfunction "C13_P$43") (pintype "passive"))
    )
    (net (code "132") (name "unconnected-(J5-C14-PadP$44)") (class "Default")
      (node (ref "J5") (pin "P$44") (pinfunction "C14_P$44") (pintype "passive"))
    )
    (net (code "133") (name "unconnected-(J5-C23-PadP$53)") (class "Default")
      (node (ref "J5") (pin "P$53") (pinfunction "C23_P$53") (pintype "passive"))
    )
    (net (code "134") (name "unconnected-(J5-D12-PadP$12)") (class "Default")
      (node (ref "J5") (pin "P$12") (pinfunction "D12_P$12") (pintype "passive"))
    )
    (net (code "135") (name "unconnected-(J5-D13-PadP$13)") (class "Default")
      (node (ref "J5") (pin "P$13") (pinfunction "D13_P$13") (pintype "passive"))
    )
    (net (code "136") (name "unconnected-(J5-D14-PadP$14)") (class "Default")
      (node (ref "J5") (pin "P$14") (pinfunction "D14_P$14") (pintype "passive"))
    )
    (net (code "137") (name "unconnected-(J5-D23-PadP$23)") (class "Default")
      (node (ref "J5") (pin "P$23") (pinfunction "D23_P$23") (pintype "passive"))
    )
    (net (code "138") (name "unconnected-(J6-C12-PadP$42)") (class "Default")
      (node (ref "J6") (pin "P$42") (pinfunction "C12_P$42") (pintype "passive"))
    )
    (net (code "139") (name "unconnected-(J6-C13-PadP$43)") (class "Default")
      (node (ref "J6") (pin "P$43") (pinfunction "C13_P$43") (pintype "passive"))
    )
    (net (code "140") (name "unconnected-(J6-C14-PadP$44)") (class "Default")
      (node (ref "J6") (pin "P$44") (pinfunction "C14_P$44") (pintype "passive"))
    )
    (net (code "141") (name "unconnected-(J6-C23-PadP$53)") (class "Default")
      (node (ref "J6") (pin "P$53") (pinfunction "C23_P$53") (pintype "passive"))
    )
    (net (code "142") (name "unconnected-(J6-D12-PadP$12)") (class "Default")
      (node (ref "J6") (pin "P$12") (pinfunction "D12_P$12") (pintype "passive"))
    )
    (net (code "143") (name "unconnected-(J6-D13-PadP$13)") (class "Default")
      (node (ref "J6") (pin "P$13") (pinfunction "D13_P$13") (pintype "passive"))
    )
    (net (code "144") (name "unconnected-(J6-D14-PadP$14)") (class "Default")
      (node (ref "J6") (pin "P$14") (pinfunction "D14_P$14") (pintype "passive"))
    )
    (net (code "145") (name "unconnected-(J6-D23-PadP$23)") (class "Default")
      (node (ref "J6") (pin "P$23") (pinfunction "D23_P$23") (pintype "passive"))
    )
  )
)
